# module_decode_opcodes.net
KiCad netlist of a schematic drawn in EAGLE
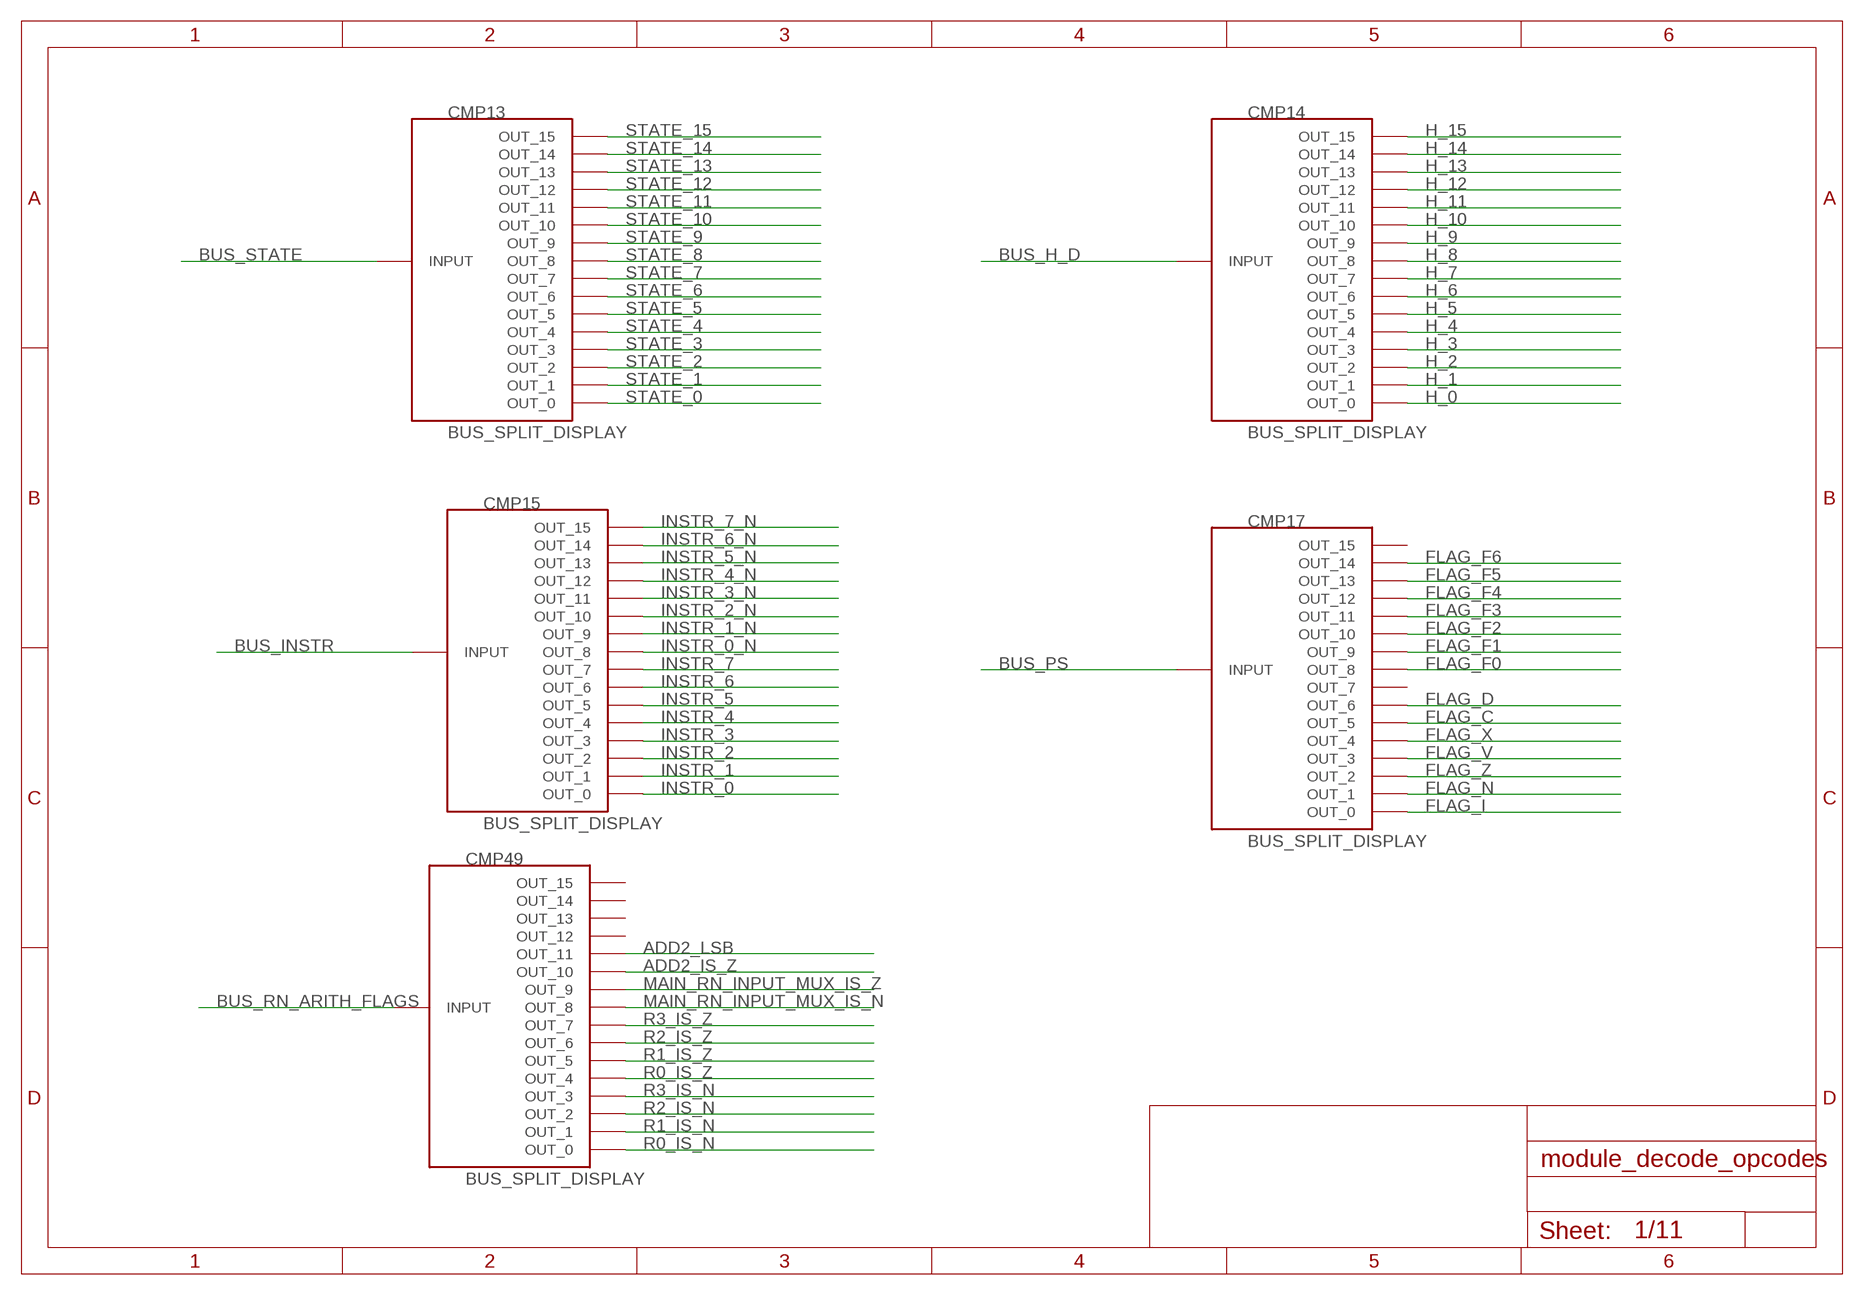
[diagram p0: schematic, sheet 1]
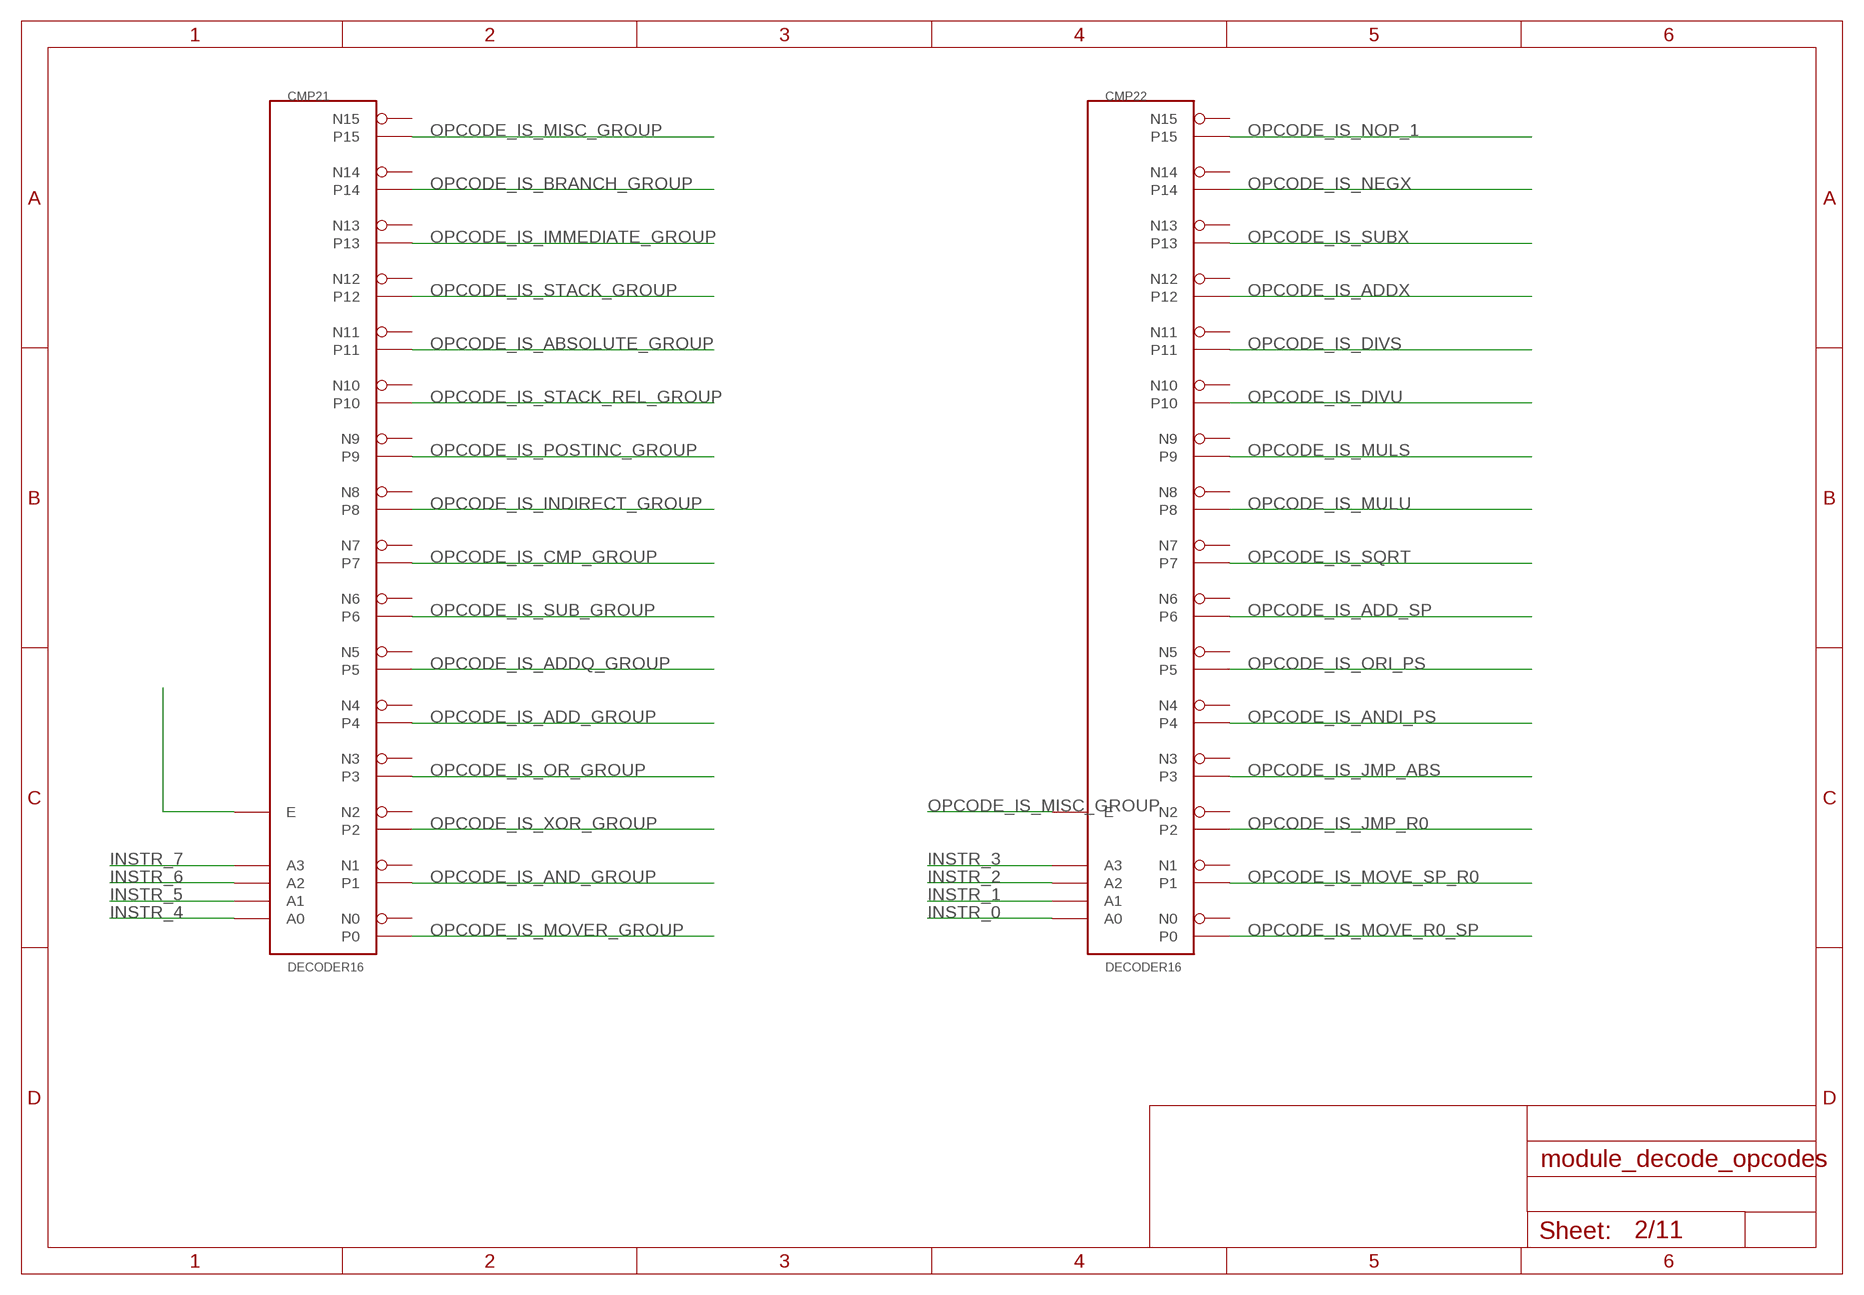
[diagram p1: schematic, sheet 2]
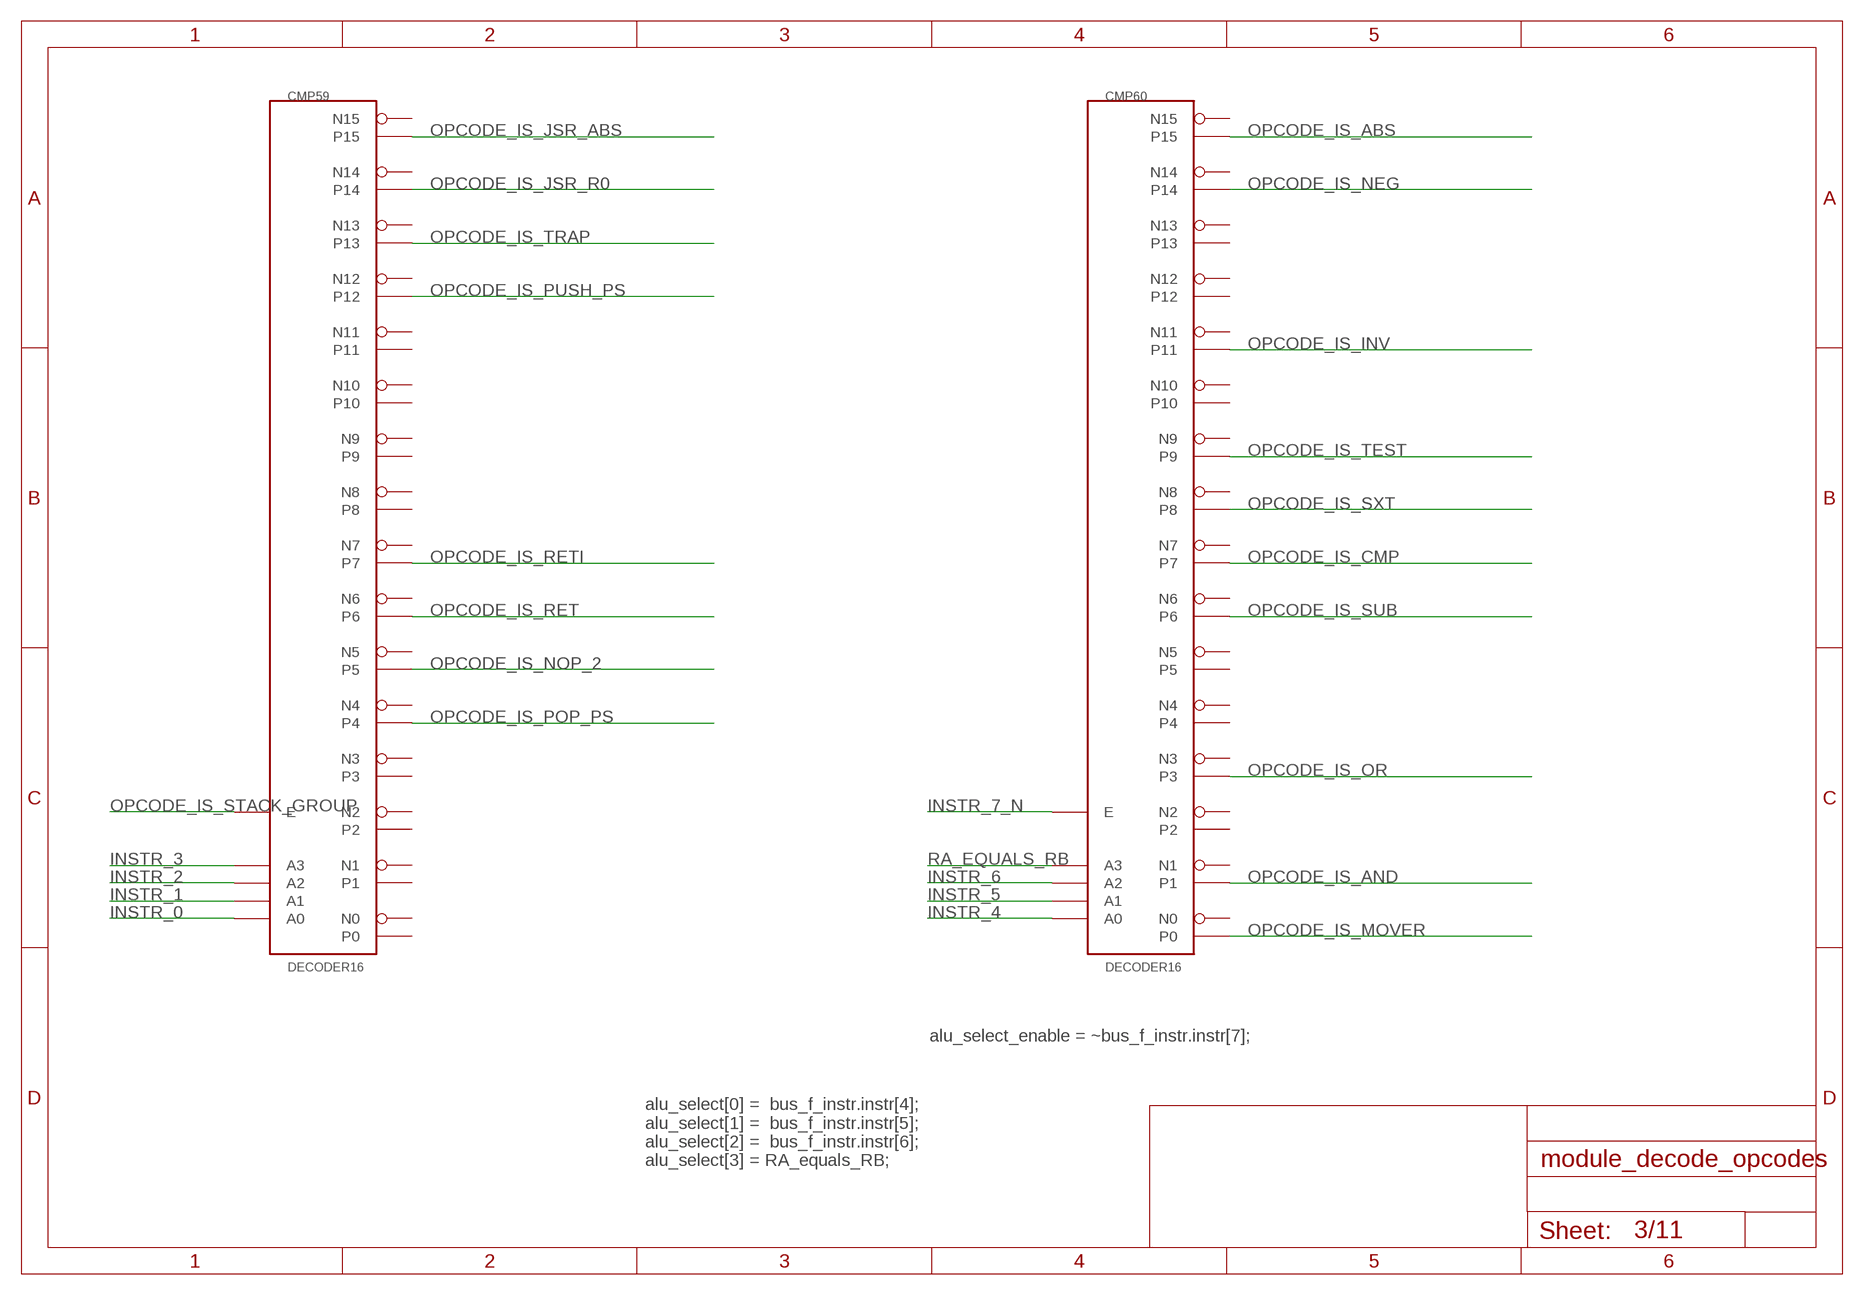
[diagram p2: schematic, sheet 3]
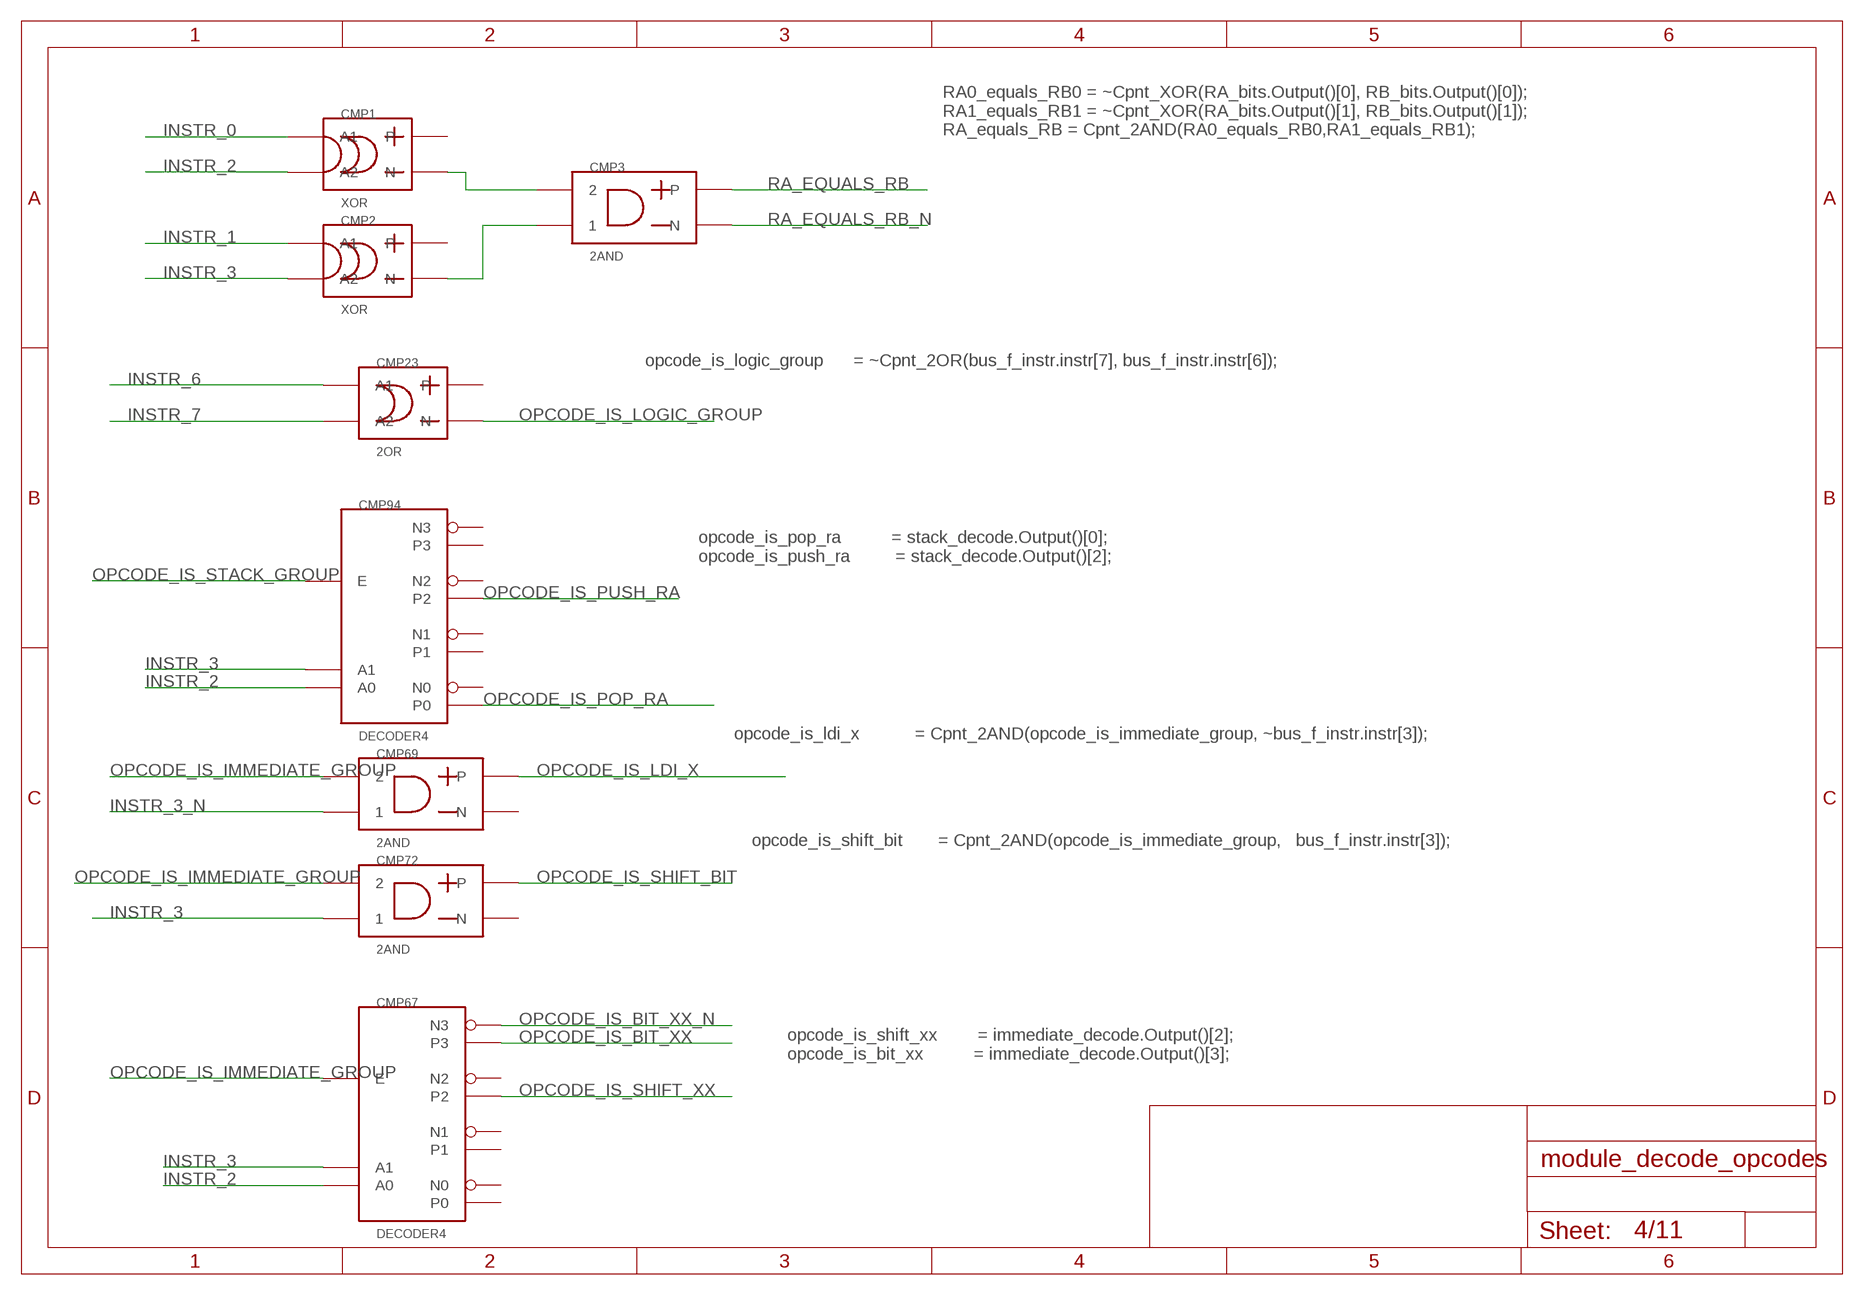
[diagram p3: schematic, sheet 4]
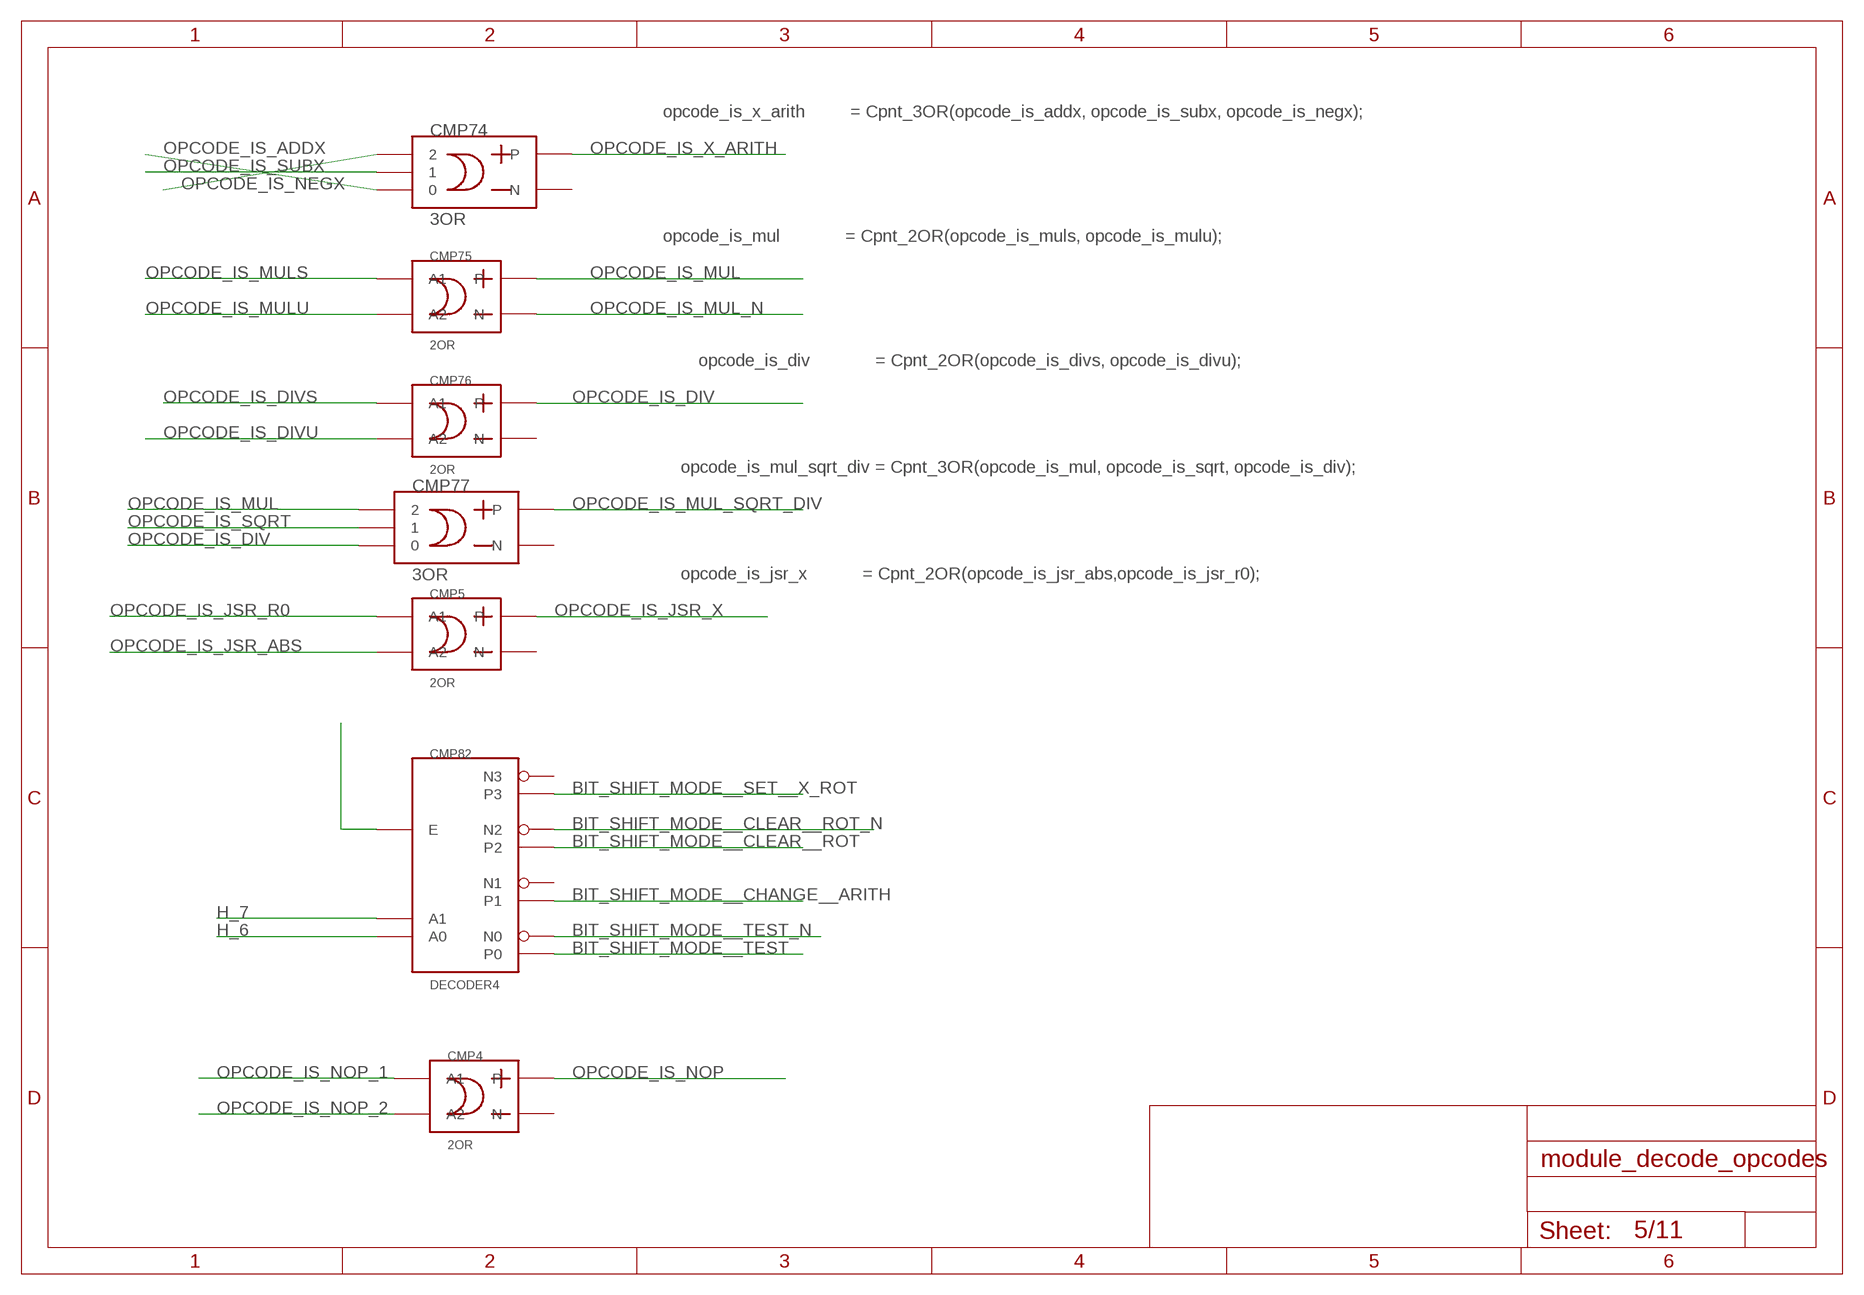
[diagram p4: schematic, sheet 5]
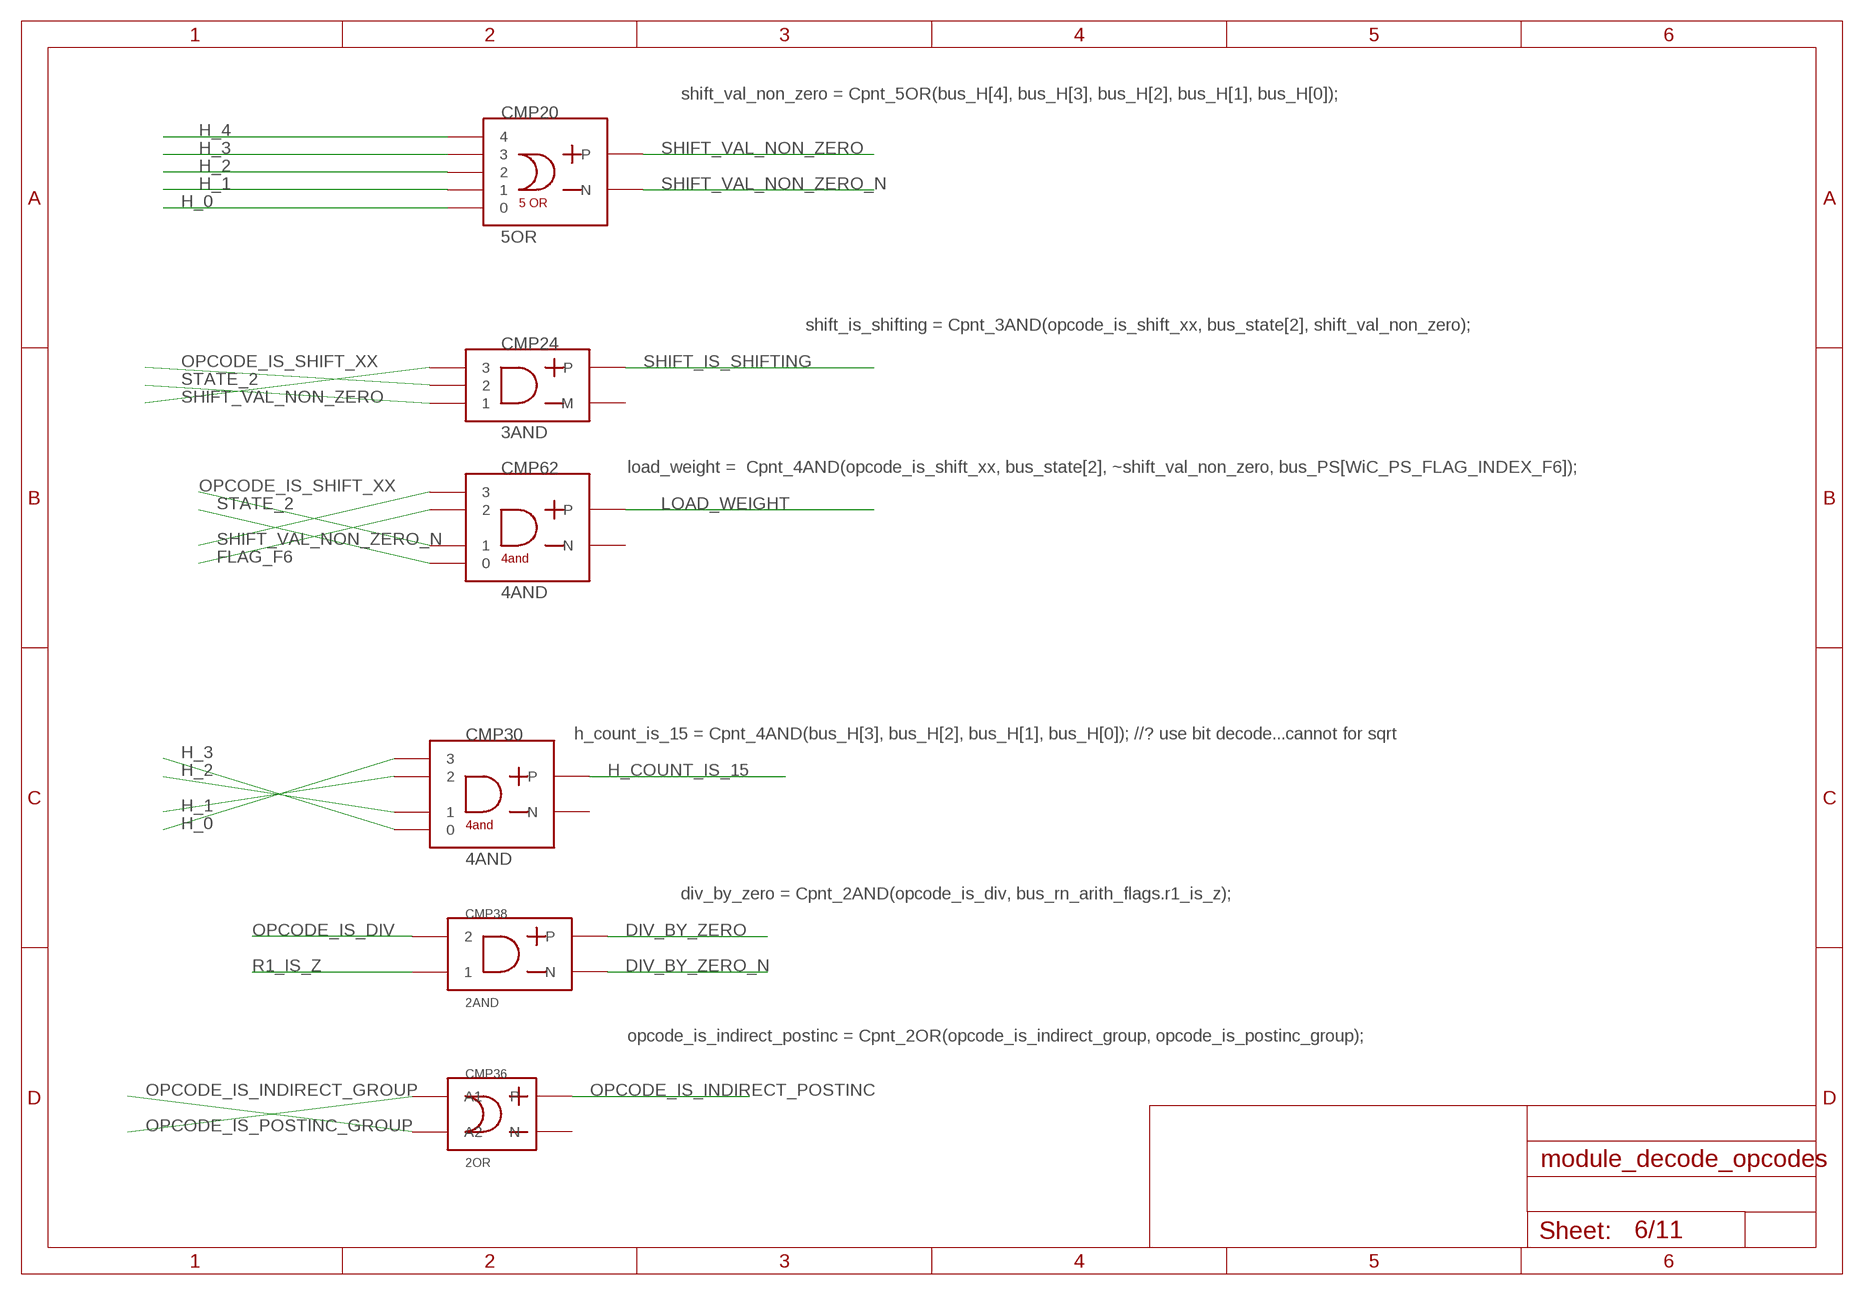
[diagram p5: schematic, sheet 6]
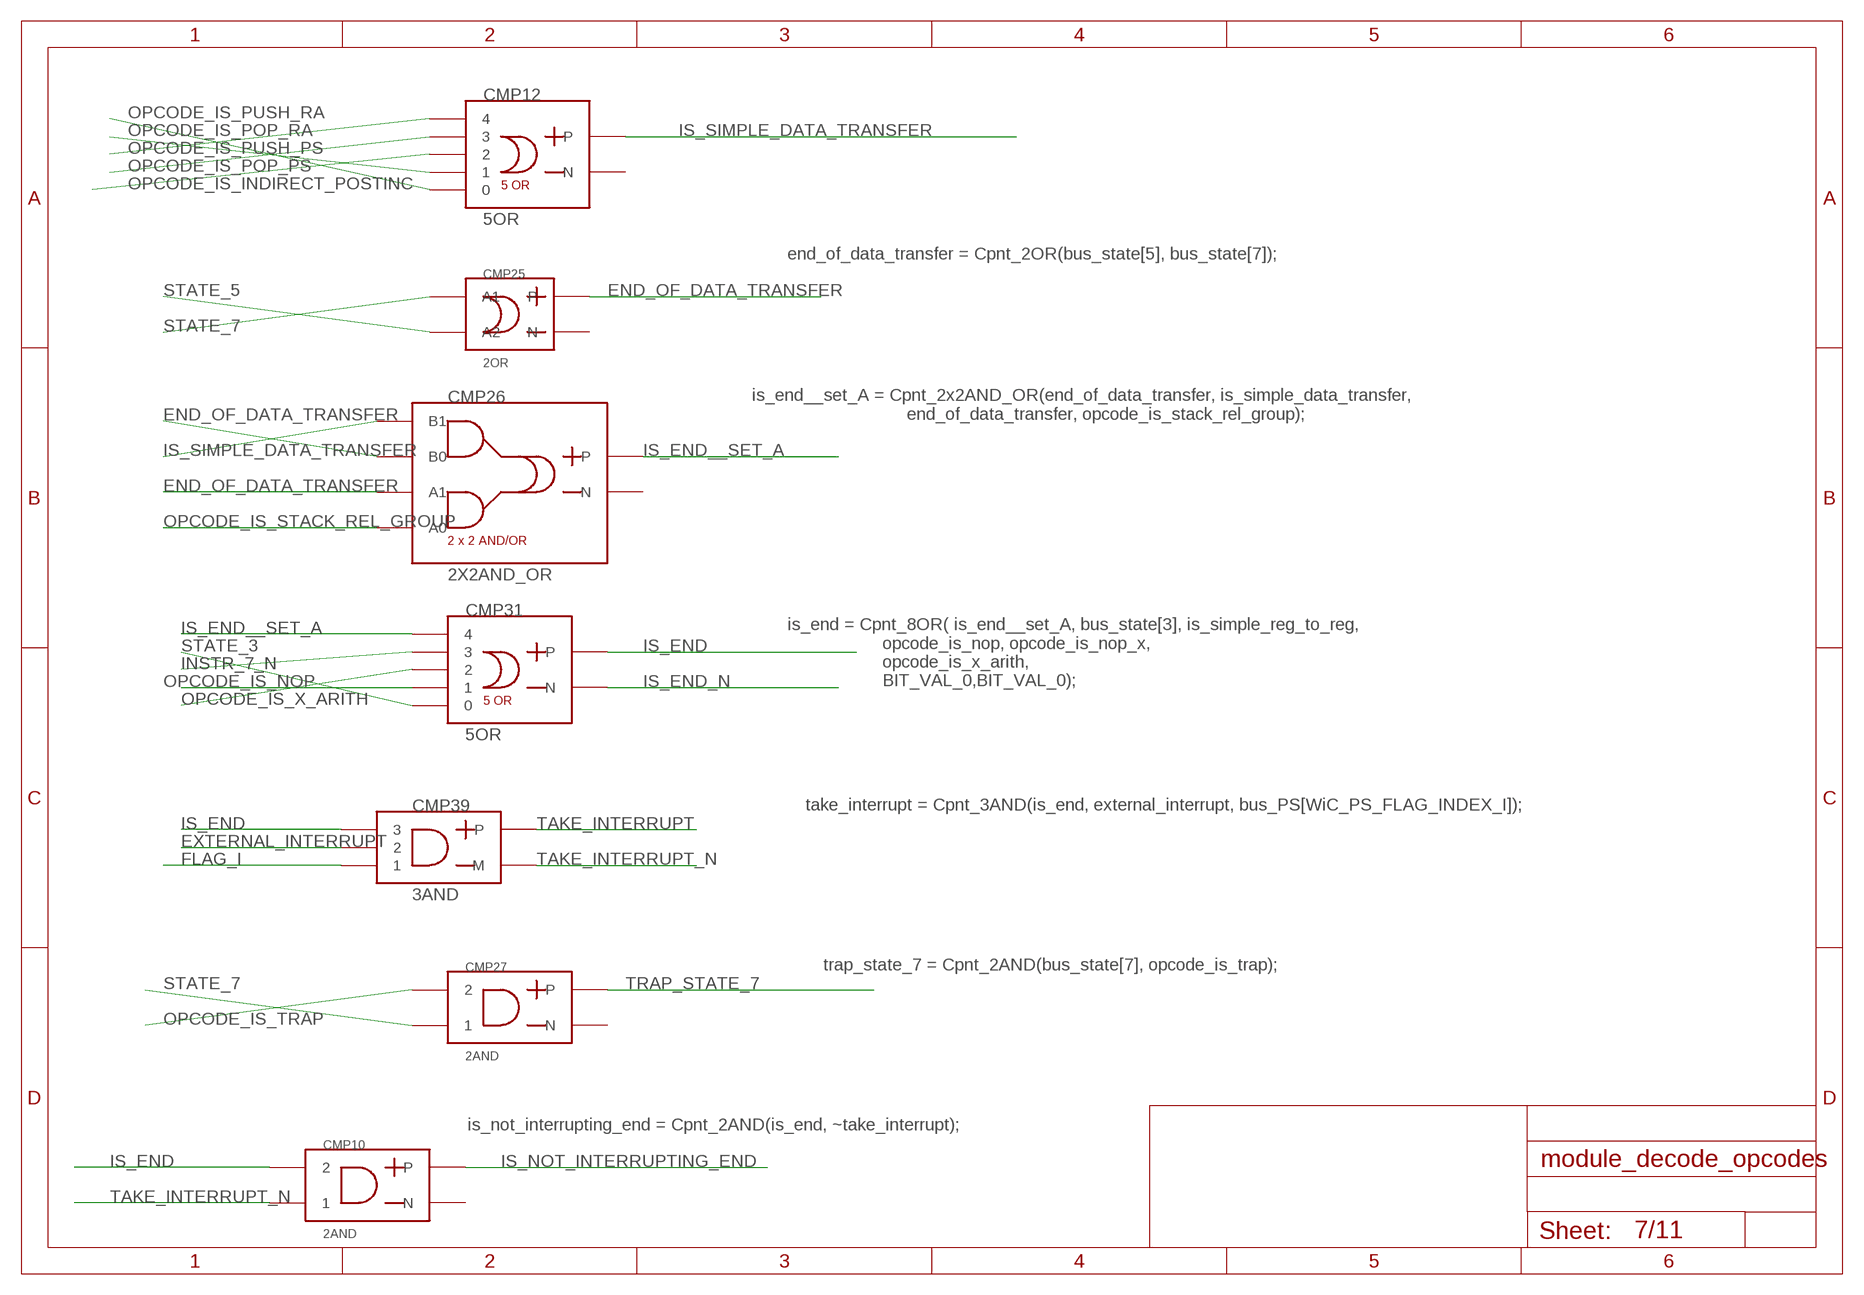
[diagram p6: schematic, sheet 7]
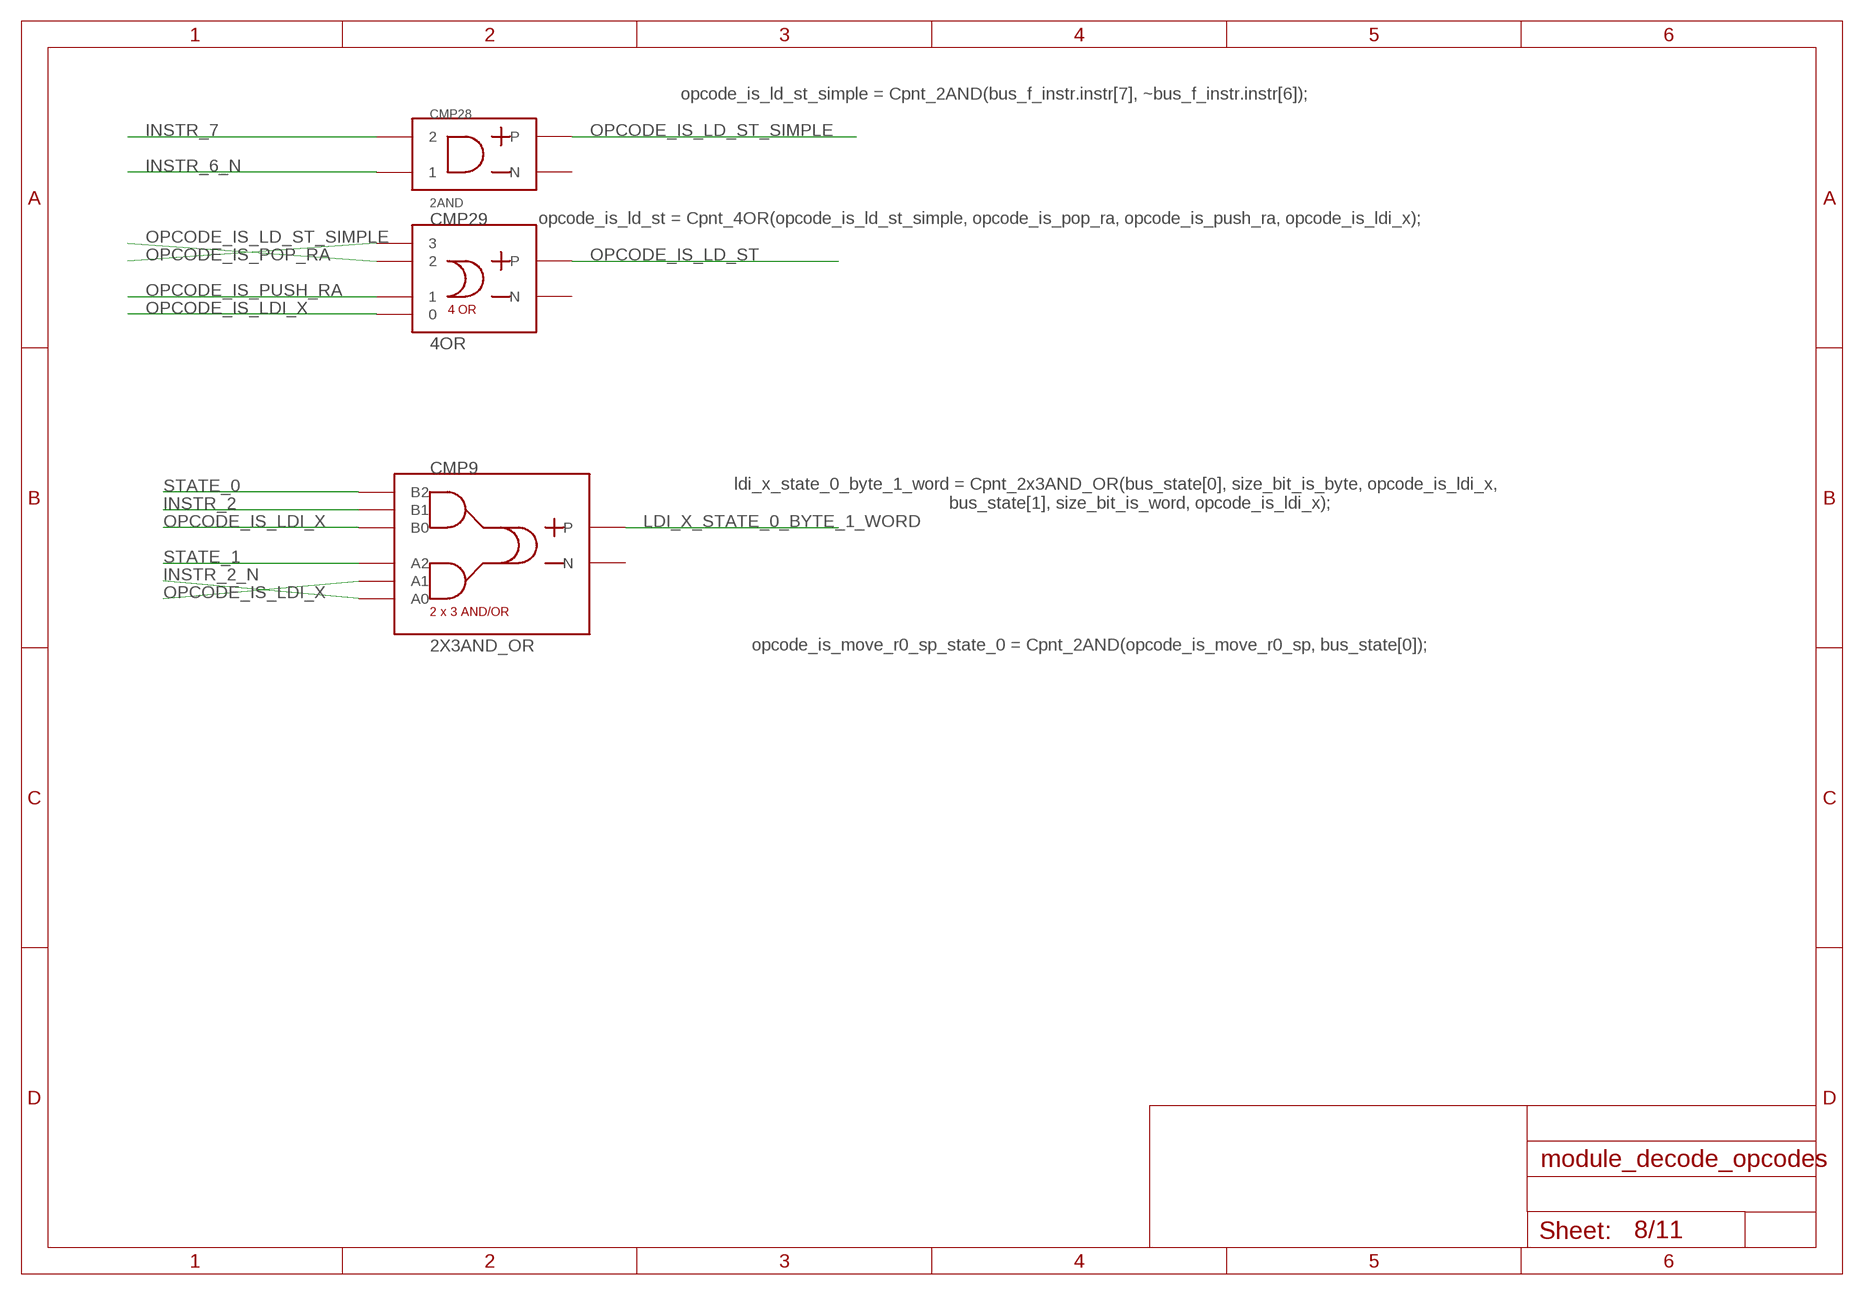
[diagram p7: schematic, sheet 8]
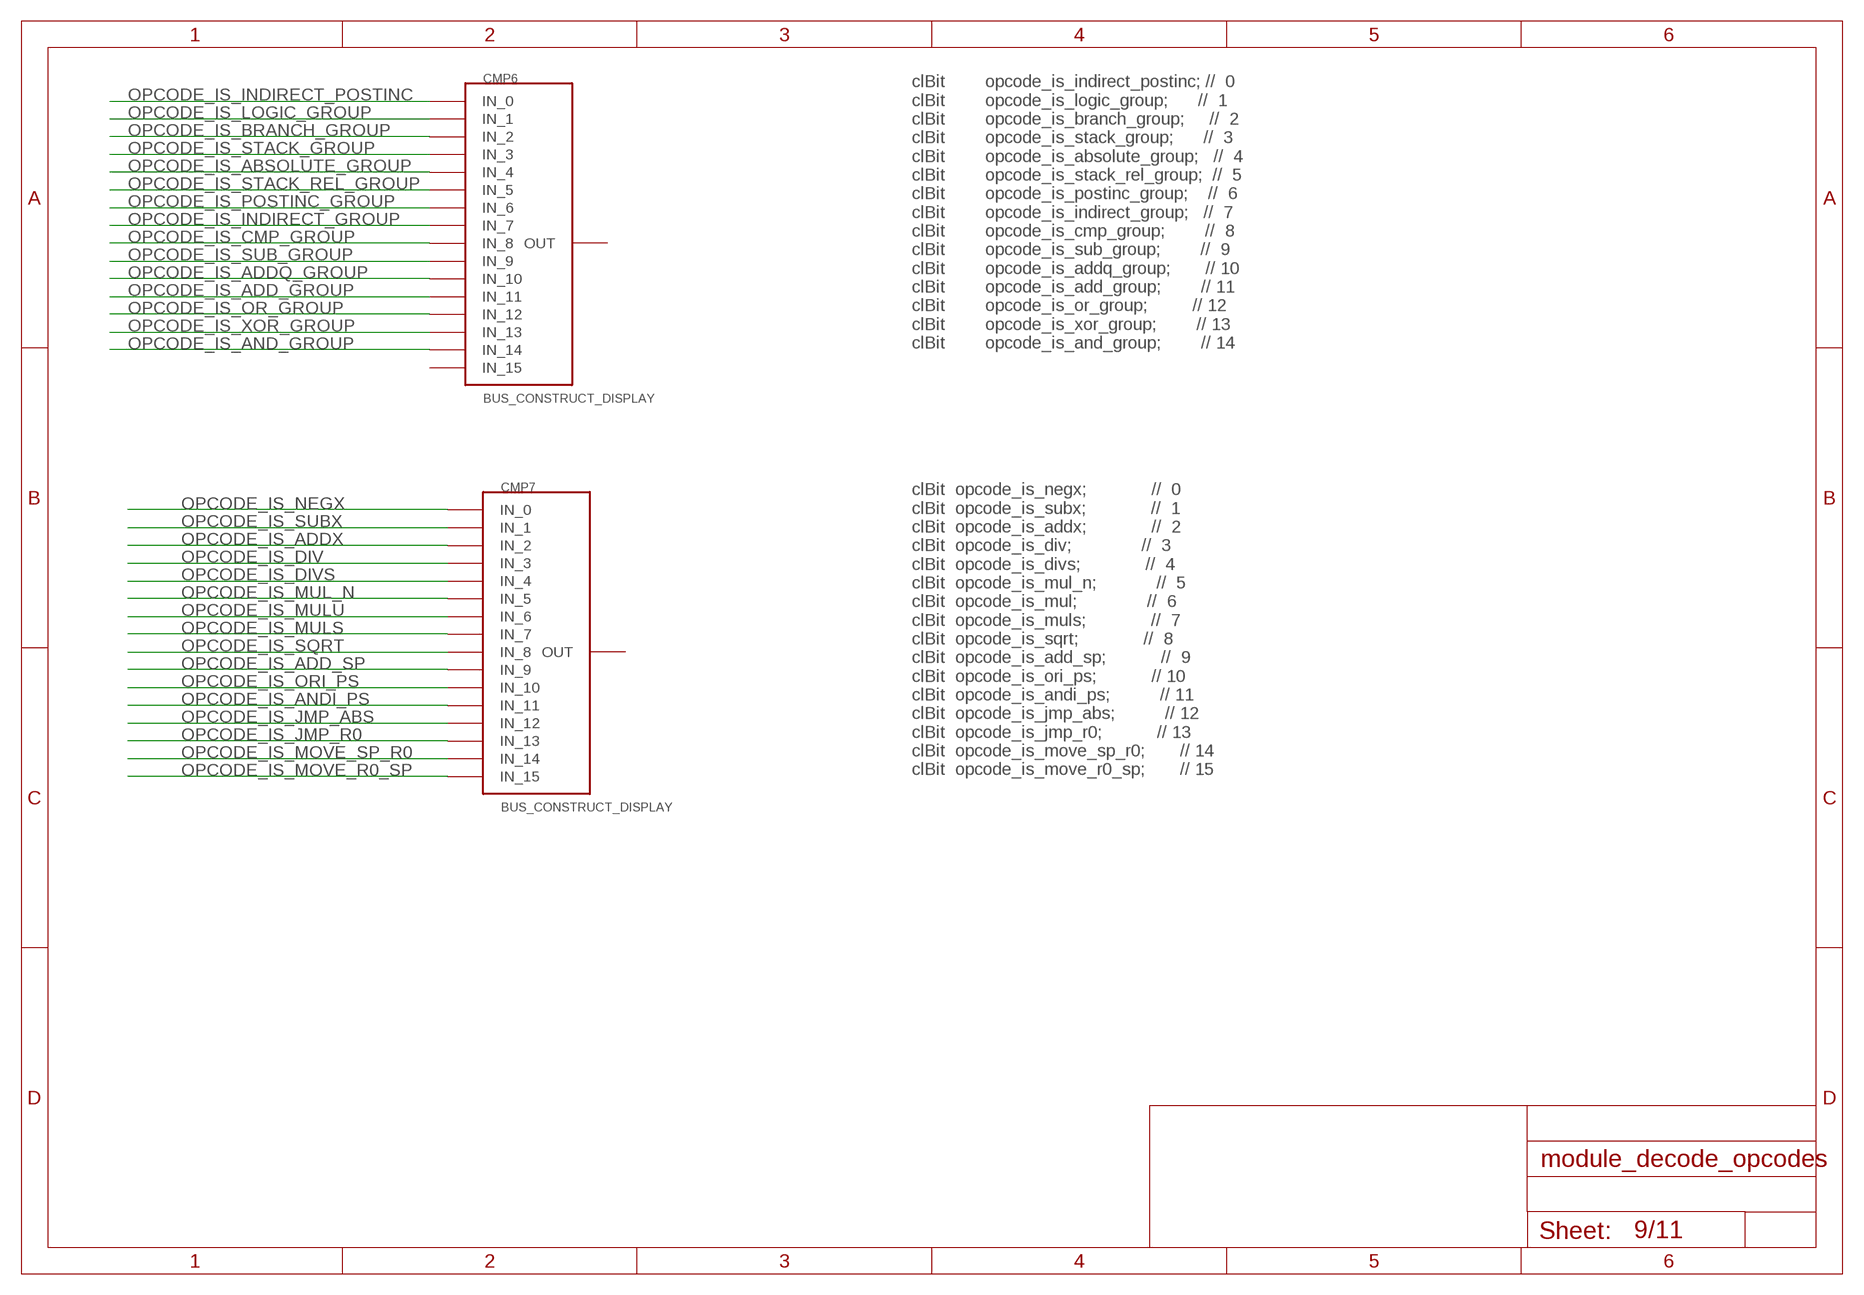
[diagram p8: schematic, sheet 9]
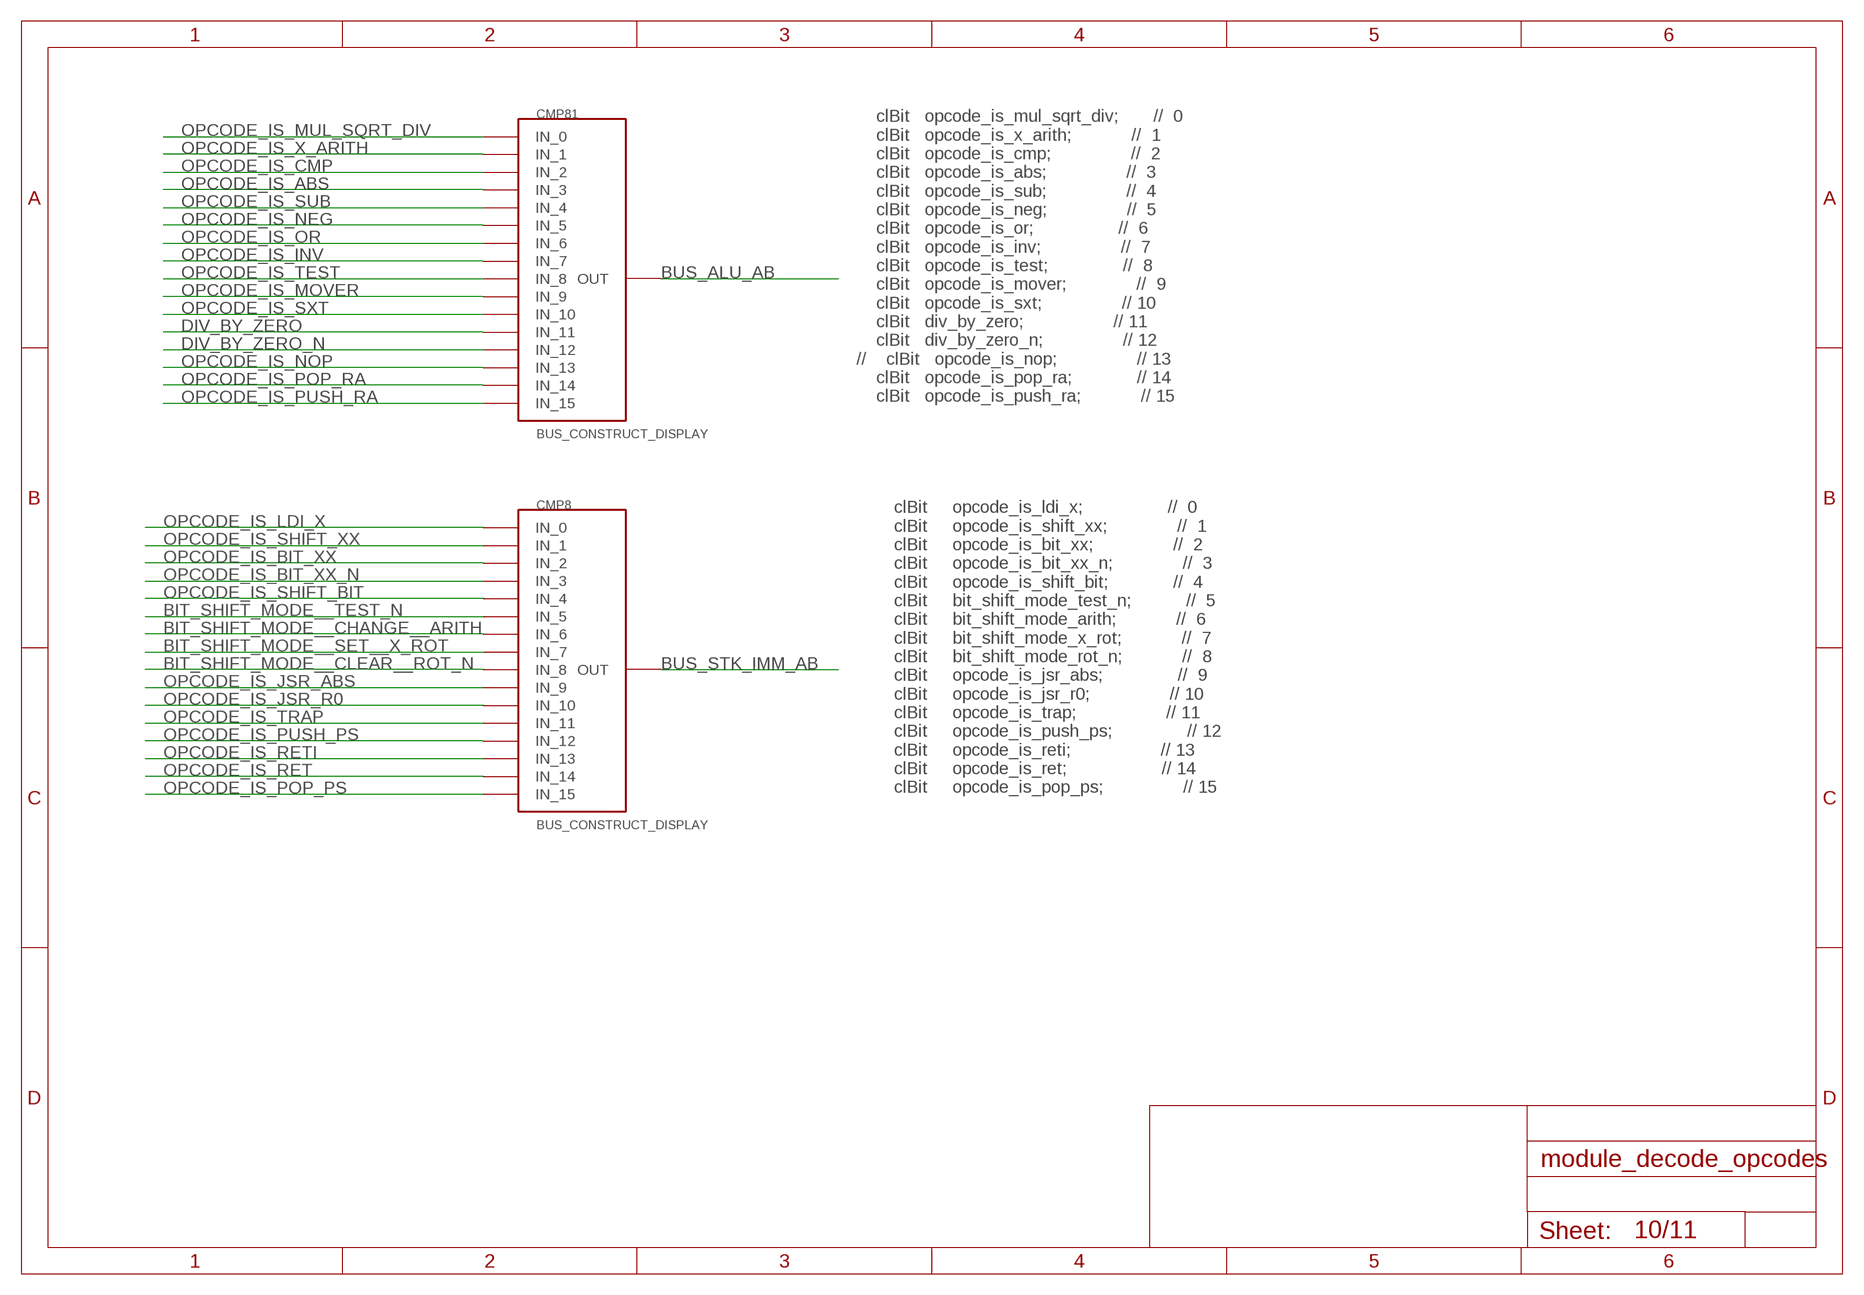
[diagram p9: schematic, sheet 10]
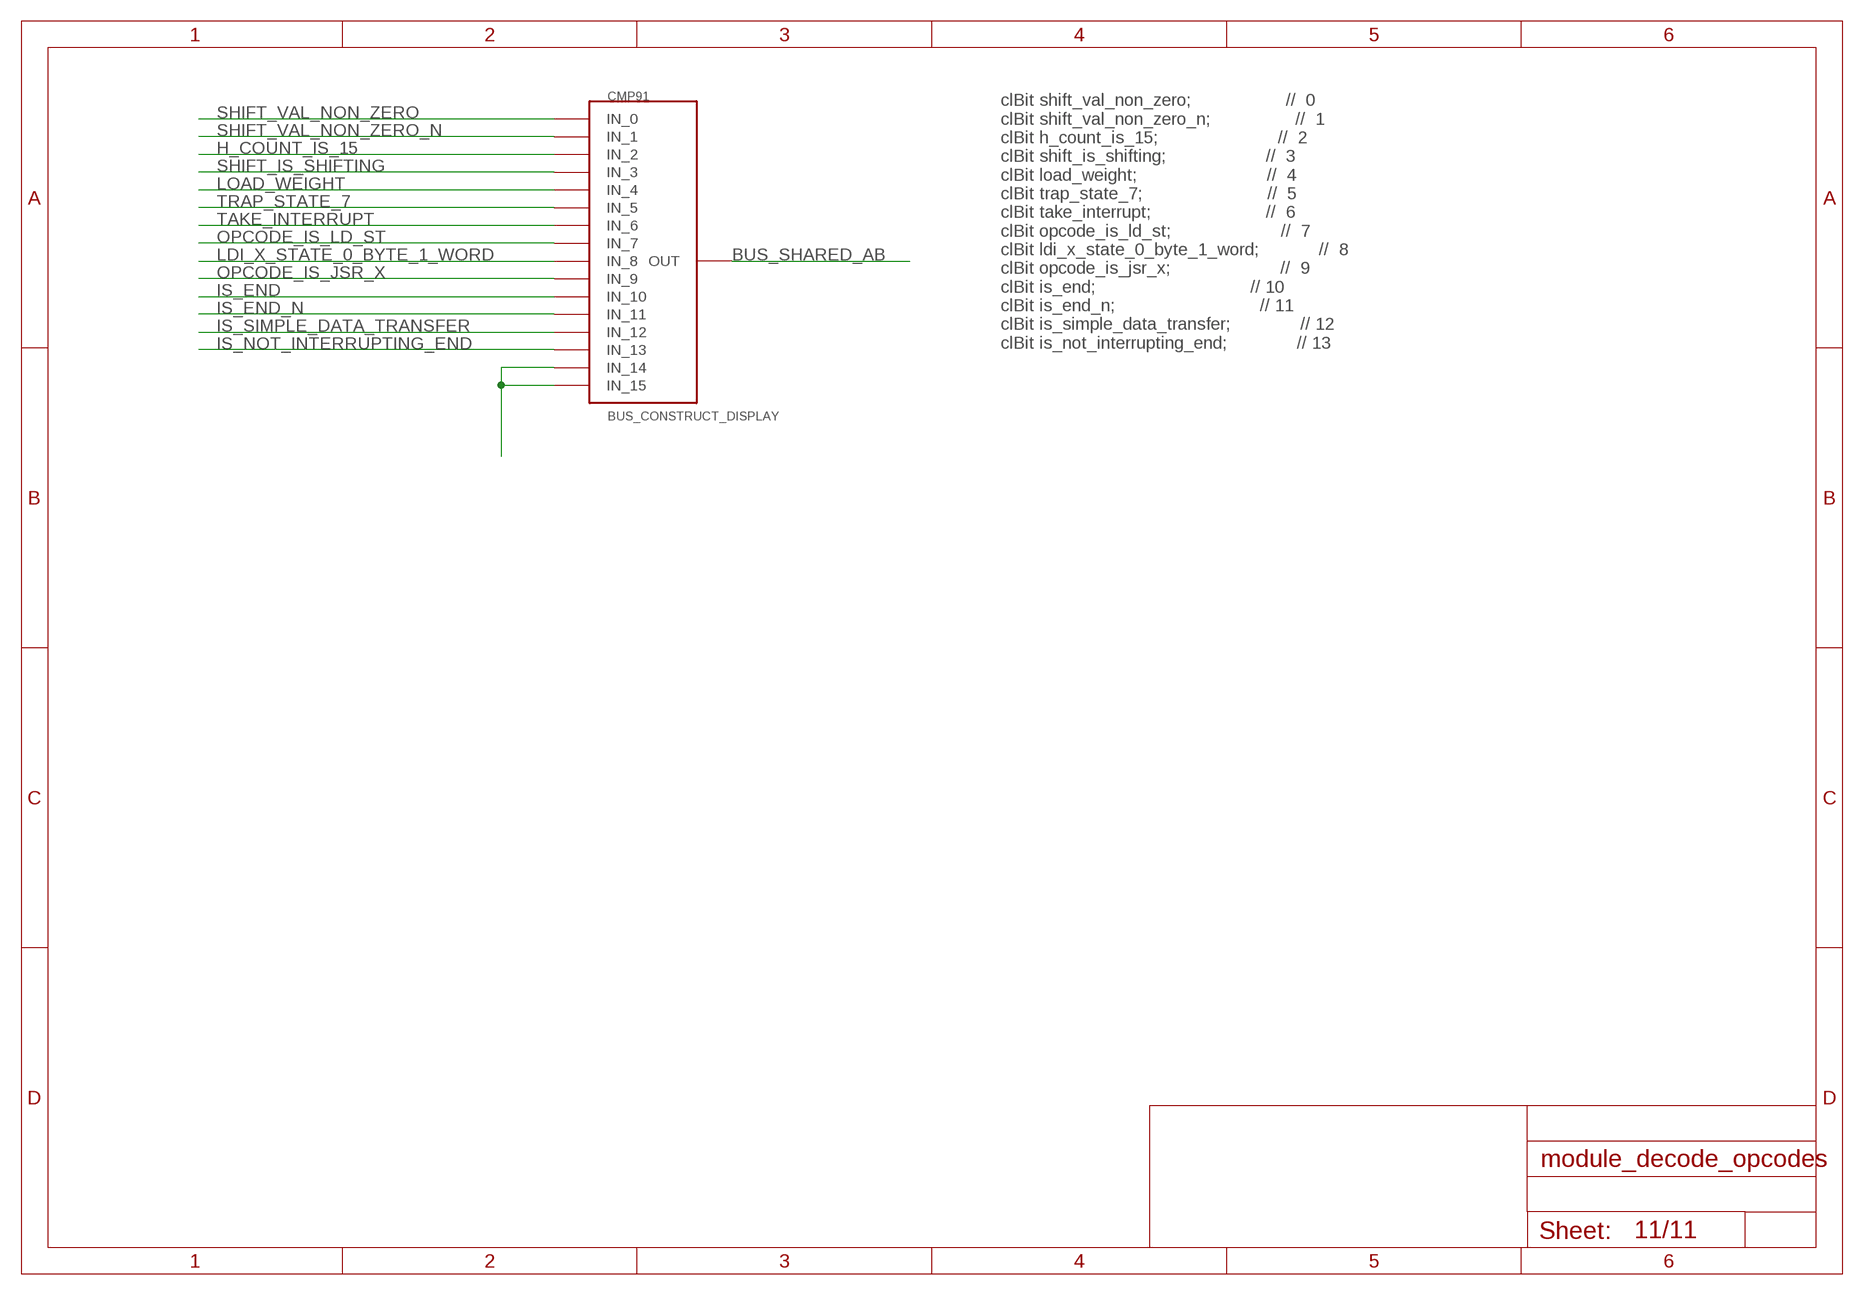
[diagram p10: schematic, sheet 11]

(export (version "E")
  (design (tool "Eeschema 10.0.6"))
  (components
    (comp (ref "CMP9")
      (value "2X3AND_OR")
      (footprint "eagle-import:2X3AND_OR")
      (libsource (lib "eagle-import") (part "2X3AND_OR"))
    )
    (comp (ref "CMP28")
      (value "2AND")
      (footprint "eagle-import:2AND")
      (libsource (lib "eagle-import") (part "2AND"))
    )
    (comp (ref "CMP29")
      (value "4OR")
      (footprint "eagle-import:4OR")
      (libsource (lib "eagle-import") (part "4OR"))
    )
    (comp (ref "CMP4")
      (value "2OR")
      (footprint "eagle-import:2OR")
      (libsource (lib "eagle-import") (part "2OR"))
    )
    (comp (ref "CMP5")
      (value "2OR")
      (footprint "eagle-import:2OR")
      (libsource (lib "eagle-import") (part "2OR"))
    )
    (comp (ref "CMP74")
      (value "3OR")
      (footprint "eagle-import:3OR")
      (libsource (lib "eagle-import") (part "3OR"))
    )
    (comp (ref "CMP75")
      (value "2OR")
      (footprint "eagle-import:2OR")
      (libsource (lib "eagle-import") (part "2OR"))
    )
    (comp (ref "CMP76")
      (value "2OR")
      (footprint "eagle-import:2OR")
      (libsource (lib "eagle-import") (part "2OR"))
    )
    (comp (ref "CMP77")
      (value "3OR")
      (footprint "eagle-import:3OR")
      (libsource (lib "eagle-import") (part "3OR"))
    )
    (comp (ref "CMP82")
      (value "DECODER4")
      (footprint "eagle-import:DECODER4")
      (libsource (lib "eagle-import") (part "DECODER4"))
    )
    (comp (ref "CMP91")
      (value "BUS_CONSTRUCT_DISPLAY")
      (footprint "eagle-import:BUS_SPLIT_DISPLAY")
      (libsource (lib "eagle-import") (part "BUS_CONSTRUCT_DISPLAY"))
    )
    (comp (ref "CMP1")
      (value "XOR")
      (footprint "eagle-import:XOR")
      (libsource (lib "eagle-import") (part "XOR"))
    )
    (comp (ref "CMP2")
      (value "XOR")
      (footprint "eagle-import:XOR")
      (libsource (lib "eagle-import") (part "XOR"))
    )
    (comp (ref "CMP3")
      (value "2AND")
      (footprint "eagle-import:2AND")
      (libsource (lib "eagle-import") (part "2AND"))
    )
    (comp (ref "CMP23")
      (value "2OR")
      (footprint "eagle-import:2OR")
      (libsource (lib "eagle-import") (part "2OR"))
    )
    (comp (ref "CMP67")
      (value "DECODER4")
      (footprint "eagle-import:DECODER4")
      (libsource (lib "eagle-import") (part "DECODER4"))
    )
    (comp (ref "CMP69")
      (value "2AND")
      (footprint "eagle-import:2AND")
      (libsource (lib "eagle-import") (part "2AND"))
    )
    (comp (ref "CMP72")
      (value "2AND")
      (footprint "eagle-import:2AND")
      (libsource (lib "eagle-import") (part "2AND"))
    )
    (comp (ref "CMP94")
      (value "DECODER4")
      (footprint "eagle-import:DECODER4")
      (libsource (lib "eagle-import") (part "DECODER4"))
    )
    (comp (ref "CMP59")
      (value "DECODER16")
      (footprint "eagle-import:DECODER16")
      (libsource (lib "eagle-import") (part "DECODER16"))
    )
    (comp (ref "CMP60")
      (value "DECODER16")
      (footprint "eagle-import:DECODER16")
      (libsource (lib "eagle-import") (part "DECODER16"))
    )
    (comp (ref "CMP13")
      (value "BUS_SPLIT_DISPLAY")
      (footprint "eagle-import:BUS_SPLIT_DISPLAY")
      (libsource (lib "eagle-import") (part "BUS_SPLIT_DISPLAY"))
    )
    (comp (ref "CMP14")
      (value "BUS_SPLIT_DISPLAY")
      (footprint "eagle-import:BUS_SPLIT_DISPLAY")
      (libsource (lib "eagle-import") (part "BUS_SPLIT_DISPLAY"))
    )
    (comp (ref "CMP15")
      (value "BUS_SPLIT_DISPLAY")
      (footprint "eagle-import:BUS_SPLIT_DISPLAY")
      (libsource (lib "eagle-import") (part "BUS_SPLIT_DISPLAY"))
    )
    (comp (ref "CMP17")
      (value "BUS_SPLIT_DISPLAY")
      (footprint "eagle-import:BUS_SPLIT_DISPLAY")
      (libsource (lib "eagle-import") (part "BUS_SPLIT_DISPLAY"))
    )
    (comp (ref "CMP49")
      (value "BUS_SPLIT_DISPLAY")
      (footprint "eagle-import:BUS_SPLIT_DISPLAY")
      (libsource (lib "eagle-import") (part "BUS_SPLIT_DISPLAY"))
    )
    (comp (ref "CMP10")
      (value "2AND")
      (footprint "eagle-import:2AND")
      (libsource (lib "eagle-import") (part "2AND"))
    )
    (comp (ref "CMP12")
      (value "5OR")
      (footprint "eagle-import:5OR")
      (libsource (lib "eagle-import") (part "5OR"))
    )
    (comp (ref "CMP25")
      (value "2OR")
      (footprint "eagle-import:2OR")
      (libsource (lib "eagle-import") (part "2OR"))
    )
    (comp (ref "CMP26")
      (value "2X2AND_OR")
      (footprint "eagle-import:2X2AND_OR")
      (libsource (lib "eagle-import") (part "2X2AND_OR"))
    )
    (comp (ref "CMP27")
      (value "2AND")
      (footprint "eagle-import:2AND")
      (libsource (lib "eagle-import") (part "2AND"))
    )
    (comp (ref "CMP31")
      (value "5OR")
      (footprint "eagle-import:5OR")
      (libsource (lib "eagle-import") (part "5OR"))
    )
    (comp (ref "CMP39")
      (value "3AND")
      (footprint "eagle-import:3AND")
      (libsource (lib "eagle-import") (part "3AND"))
    )
    (comp (ref "CMP21")
      (value "DECODER16")
      (footprint "eagle-import:DECODER16")
      (libsource (lib "eagle-import") (part "DECODER16"))
    )
    (comp (ref "CMP22")
      (value "DECODER16")
      (footprint "eagle-import:DECODER16")
      (libsource (lib "eagle-import") (part "DECODER16"))
    )
    (comp (ref "CMP6")
      (value "BUS_CONSTRUCT_DISPLAY")
      (footprint "eagle-import:BUS_SPLIT_DISPLAY")
      (libsource (lib "eagle-import") (part "BUS_CONSTRUCT_DISPLAY"))
    )
    (comp (ref "CMP7")
      (value "BUS_CONSTRUCT_DISPLAY")
      (footprint "eagle-import:BUS_SPLIT_DISPLAY")
      (libsource (lib "eagle-import") (part "BUS_CONSTRUCT_DISPLAY"))
    )
    (comp (ref "CMP8")
      (value "BUS_CONSTRUCT_DISPLAY")
      (footprint "eagle-import:BUS_SPLIT_DISPLAY")
      (libsource (lib "eagle-import") (part "BUS_CONSTRUCT_DISPLAY"))
    )
    (comp (ref "CMP81")
      (value "BUS_CONSTRUCT_DISPLAY")
      (footprint "eagle-import:BUS_SPLIT_DISPLAY")
      (libsource (lib "eagle-import") (part "BUS_CONSTRUCT_DISPLAY"))
    )
    (comp (ref "CMP20")
      (value "5OR")
      (footprint "eagle-import:5OR")
      (libsource (lib "eagle-import") (part "5OR"))
    )
    (comp (ref "CMP24")
      (value "3AND")
      (footprint "eagle-import:3AND")
      (libsource (lib "eagle-import") (part "3AND"))
    )
    (comp (ref "CMP30")
      (value "4AND")
      (footprint "eagle-import:4AND")
      (libsource (lib "eagle-import") (part "4AND"))
    )
    (comp (ref "CMP36")
      (value "2OR")
      (footprint "eagle-import:2OR")
      (libsource (lib "eagle-import") (part "2OR"))
    )
    (comp (ref "CMP38")
      (value "2AND")
      (footprint "eagle-import:2AND")
      (libsource (lib "eagle-import") (part "2AND"))
    )
    (comp (ref "CMP62")
      (value "4AND")
      (footprint "eagle-import:4AND")
      (libsource (lib "eagle-import") (part "4AND"))
    )
  )
  (nets
    (net (code "1") (name "ADD2_IS_Z") (class "Default")
      (node (ref "CMP49") (pin "P$11") (pinfunction "OUT_10_P$11") (pintype "output"))
    )
    (net (code "2") (name "ADD2_LSB") (class "Default")
      (node (ref "CMP49") (pin "P$12") (pinfunction "OUT_11_P$12") (pintype "output"))
    )
    (net (code "3") (name "BIT_SHIFT_MODE__CHANGE__ARITH") (class "Default")
      (node (ref "CMP8") (pin "P$7") (pinfunction "IN_6_P$7") (pintype "input"))
      (node (ref "CMP82") (pin "P1") (pinfunction "P1_P1") (pintype "output"))
    )
    (net (code "4") (name "BIT_SHIFT_MODE__CLEAR__ROT") (class "Default")
      (node (ref "CMP82") (pin "P2") (pinfunction "P2_P2") (pintype "output"))
    )
    (net (code "5") (name "BIT_SHIFT_MODE__CLEAR__ROT_N") (class "Default")
      (node (ref "CMP8") (pin "P$9") (pinfunction "IN_8_P$9") (pintype "input"))
      (node (ref "CMP82") (pin "N2") (pinfunction "N2_N2") (pintype "output"))
    )
    (net (code "6") (name "BIT_SHIFT_MODE__SET__X_ROT") (class "Default")
      (node (ref "CMP8") (pin "P$8") (pinfunction "IN_7_P$8") (pintype "input"))
      (node (ref "CMP82") (pin "P3") (pinfunction "P3_P3") (pintype "output"))
    )
    (net (code "7") (name "BIT_SHIFT_MODE__TEST") (class "Default")
      (node (ref "CMP82") (pin "P0") (pinfunction "P0_P0") (pintype "output"))
    )
    (net (code "8") (name "BIT_SHIFT_MODE__TEST_N") (class "Default")
      (node (ref "CMP8") (pin "P$6") (pinfunction "IN_5_P$6") (pintype "input"))
      (node (ref "CMP82") (pin "N0") (pinfunction "N0_N0") (pintype "output"))
    )
    (net (code "9") (name "BUS_ALU_AB") (class "Default")
      (node (ref "CMP81") (pin "INPUT") (pinfunction "OUT_INPUT") (pintype "output"))
    )
    (net (code "10") (name "BUS_H_D") (class "Default")
      (node (ref "CMP14") (pin "INPUT") (pinfunction "INPUT_INPUT") (pintype "input"))
    )
    (net (code "11") (name "BUS_INSTR") (class "Default")
      (node (ref "CMP15") (pin "INPUT") (pinfunction "INPUT_INPUT") (pintype "input"))
    )
    (net (code "12") (name "BUS_PS") (class "Default")
      (node (ref "CMP17") (pin "INPUT") (pinfunction "INPUT_INPUT") (pintype "input"))
    )
    (net (code "13") (name "BUS_RN_ARITH_FLAGS") (class "Default")
      (node (ref "CMP49") (pin "INPUT") (pinfunction "INPUT_INPUT") (pintype "input"))
    )
    (net (code "14") (name "BUS_SHARED_AB") (class "Default")
      (node (ref "CMP91") (pin "INPUT") (pinfunction "OUT_INPUT") (pintype "output"))
    )
    (net (code "15") (name "BUS_STATE") (class "Default")
      (node (ref "CMP13") (pin "INPUT") (pinfunction "INPUT_INPUT") (pintype "input"))
    )
    (net (code "16") (name "BUS_STK_IMM_AB") (class "Default")
      (node (ref "CMP8") (pin "INPUT") (pinfunction "OUT_INPUT") (pintype "output"))
    )
    (net (code "17") (name "DIV_BY_ZERO") (class "Default")
      (node (ref "CMP38") (pin "OUT_P") (pinfunction "P_OUT_P") (pintype "output"))
      (node (ref "CMP81") (pin "P$12") (pinfunction "IN_11_P$12") (pintype "input"))
    )
    (net (code "18") (name "DIV_BY_ZERO_N") (class "Default")
      (node (ref "CMP38") (pin "OUT_M") (pinfunction "N_OUT_M") (pintype "output"))
      (node (ref "CMP81") (pin "P$13") (pinfunction "IN_12_P$13") (pintype "input"))
    )
    (net (code "19") (name "END_OF_DATA_TRANSFER") (class "Default")
      (node (ref "CMP25") (pin "OUT_P") (pinfunction "P_OUT_P") (pintype "output"))
      (node (ref "CMP26") (pin "P$2") (pinfunction "A1_P$2") (pintype "input"))
      (node (ref "CMP26") (pin "P$3") (pinfunction "B0_P$3") (pintype "input"))
    )
    (net (code "20") (name "EXTERNAL_INTERRUPT") (class "Default")
      (node (ref "CMP39") (pin "P$2") (pinfunction "2_P$2") (pintype "input"))
    )
    (net (code "21") (name "FLAG_C") (class "Default")
      (node (ref "CMP17") (pin "P$6") (pinfunction "OUT_5_P$6") (pintype "output"))
    )
    (net (code "22") (name "FLAG_D") (class "Default")
      (node (ref "CMP17") (pin "P$7") (pinfunction "OUT_6_P$7") (pintype "output"))
    )
    (net (code "23") (name "FLAG_F0") (class "Default")
      (node (ref "CMP17") (pin "P$9") (pinfunction "OUT_8_P$9") (pintype "output"))
    )
    (net (code "24") (name "FLAG_F1") (class "Default")
      (node (ref "CMP17") (pin "P$10") (pinfunction "OUT_9_P$10") (pintype "output"))
    )
    (net (code "25") (name "FLAG_F2") (class "Default")
      (node (ref "CMP17") (pin "P$11") (pinfunction "OUT_10_P$11") (pintype "output"))
    )
    (net (code "26") (name "FLAG_F3") (class "Default")
      (node (ref "CMP17") (pin "P$12") (pinfunction "OUT_11_P$12") (pintype "output"))
    )
    (net (code "27") (name "FLAG_F4") (class "Default")
      (node (ref "CMP17") (pin "P$13") (pinfunction "OUT_12_P$13") (pintype "output"))
    )
    (net (code "28") (name "FLAG_F5") (class "Default")
      (node (ref "CMP17") (pin "P$14") (pinfunction "OUT_13_P$14") (pintype "output"))
    )
    (net (code "29") (name "FLAG_F6") (class "Default")
      (node (ref "CMP17") (pin "P$15") (pinfunction "OUT_14_P$15") (pintype "output"))
      (node (ref "CMP62") (pin "P$3") (pinfunction "2_P$3") (pintype "input"))
    )
    (net (code "30") (name "FLAG_I") (class "Default")
      (node (ref "CMP17") (pin "P$1") (pinfunction "OUT_0_P$1") (pintype "output"))
      (node (ref "CMP39") (pin "P$1") (pinfunction "1_P$1") (pintype "input"))
    )
    (net (code "31") (name "FLAG_N") (class "Default")
      (node (ref "CMP17") (pin "P$2") (pinfunction "OUT_1_P$2") (pintype "output"))
    )
    (net (code "32") (name "FLAG_V") (class "Default")
      (node (ref "CMP17") (pin "P$4") (pinfunction "OUT_3_P$4") (pintype "output"))
    )
    (net (code "33") (name "FLAG_X") (class "Default")
      (node (ref "CMP17") (pin "P$5") (pinfunction "OUT_4_P$5") (pintype "output"))
    )
    (net (code "34") (name "FLAG_Z") (class "Default")
      (node (ref "CMP17") (pin "P$3") (pinfunction "OUT_2_P$3") (pintype "output"))
    )
    (net (code "35") (name "H_0") (class "Default")
      (node (ref "CMP14") (pin "P$1") (pinfunction "OUT_0_P$1") (pintype "output"))
      (node (ref "CMP20") (pin "1") (pinfunction "0_1") (pintype "input"))
      (node (ref "CMP30") (pin "P$4") (pinfunction "3_P$4") (pintype "input"))
    )
    (net (code "36") (name "H_1") (class "Default")
      (node (ref "CMP14") (pin "P$2") (pinfunction "OUT_1_P$2") (pintype "output"))
      (node (ref "CMP20") (pin "2") (pinfunction "1_2") (pintype "input"))
      (node (ref "CMP30") (pin "P$3") (pinfunction "2_P$3") (pintype "input"))
    )
    (net (code "37") (name "H_2") (class "Default")
      (node (ref "CMP14") (pin "P$3") (pinfunction "OUT_2_P$3") (pintype "output"))
      (node (ref "CMP20") (pin "3") (pinfunction "2_3") (pintype "input"))
      (node (ref "CMP30") (pin "P$2") (pinfunction "1_P$2") (pintype "input"))
    )
    (net (code "38") (name "H_3") (class "Default")
      (node (ref "CMP14") (pin "P$4") (pinfunction "OUT_3_P$4") (pintype "output"))
      (node (ref "CMP20") (pin "4") (pinfunction "3_4") (pintype "input"))
      (node (ref "CMP30") (pin "P$1") (pinfunction "0_P$1") (pintype "input"))
    )
    (net (code "39") (name "H_4") (class "Default")
      (node (ref "CMP14") (pin "P$5") (pinfunction "OUT_4_P$5") (pintype "output"))
      (node (ref "CMP20") (pin "5") (pinfunction "4_5") (pintype "input"))
    )
    (net (code "40") (name "H_5") (class "Default")
      (node (ref "CMP14") (pin "P$6") (pinfunction "OUT_5_P$6") (pintype "output"))
    )
    (net (code "41") (name "H_6") (class "Default")
      (node (ref "CMP14") (pin "P$7") (pinfunction "OUT_6_P$7") (pintype "output"))
      (node (ref "CMP82") (pin "A0") (pinfunction "A0_A0") (pintype "input"))
    )
    (net (code "42") (name "H_7") (class "Default")
      (node (ref "CMP14") (pin "P$8") (pinfunction "OUT_7_P$8") (pintype "output"))
      (node (ref "CMP82") (pin "A1") (pinfunction "A1_A1") (pintype "input"))
    )
    (net (code "43") (name "H_8") (class "Default")
      (node (ref "CMP14") (pin "P$9") (pinfunction "OUT_8_P$9") (pintype "output"))
    )
    (net (code "44") (name "H_9") (class "Default")
      (node (ref "CMP14") (pin "P$10") (pinfunction "OUT_9_P$10") (pintype "output"))
    )
    (net (code "45") (name "H_10") (class "Default")
      (node (ref "CMP14") (pin "P$11") (pinfunction "OUT_10_P$11") (pintype "output"))
    )
    (net (code "46") (name "H_11") (class "Default")
      (node (ref "CMP14") (pin "P$12") (pinfunction "OUT_11_P$12") (pintype "output"))
    )
    (net (code "47") (name "H_12") (class "Default")
      (node (ref "CMP14") (pin "P$13") (pinfunction "OUT_12_P$13") (pintype "output"))
    )
    (net (code "48") (name "H_13") (class "Default")
      (node (ref "CMP14") (pin "P$14") (pinfunction "OUT_13_P$14") (pintype "output"))
    )
    (net (code "49") (name "H_14") (class "Default")
      (node (ref "CMP14") (pin "P$15") (pinfunction "OUT_14_P$15") (pintype "output"))
    )
    (net (code "50") (name "H_15") (class "Default")
      (node (ref "CMP14") (pin "P$16") (pinfunction "OUT_15_P$16") (pintype "output"))
    )
    (net (code "51") (name "H_COUNT_IS_15") (class "Default")
      (node (ref "CMP30") (pin "OUT_P") (pinfunction "P_OUT_P") (pintype "output"))
      (node (ref "CMP91") (pin "P$3") (pinfunction "IN_2_P$3") (pintype "input"))
    )
    (net (code "52") (name "INSTR_0") (class "Default")
      (node (ref "CMP1") (pin "P$1") (pinfunction "A1_P$1") (pintype "input"))
      (node (ref "CMP15") (pin "P$1") (pinfunction "OUT_0_P$1") (pintype "output"))
      (node (ref "CMP22") (pin "A0") (pinfunction "A0_A0") (pintype "input"))
      (node (ref "CMP59") (pin "A0") (pinfunction "A0_A0") (pintype "input"))
    )
    (net (code "53") (name "INSTR_0_N") (class "Default")
      (node (ref "CMP15") (pin "P$9") (pinfunction "OUT_8_P$9") (pintype "output"))
    )
    (net (code "54") (name "INSTR_1") (class "Default")
      (node (ref "CMP15") (pin "P$2") (pinfunction "OUT_1_P$2") (pintype "output"))
      (node (ref "CMP2") (pin "P$1") (pinfunction "A1_P$1") (pintype "input"))
      (node (ref "CMP22") (pin "A1") (pinfunction "A1_A1") (pintype "input"))
      (node (ref "CMP59") (pin "A1") (pinfunction "A1_A1") (pintype "input"))
    )
    (net (code "55") (name "INSTR_1_N") (class "Default")
      (node (ref "CMP15") (pin "P$10") (pinfunction "OUT_9_P$10") (pintype "output"))
    )
    (net (code "56") (name "INSTR_2") (class "Default")
      (node (ref "CMP1") (pin "P$2") (pinfunction "A2_P$2") (pintype "input"))
      (node (ref "CMP15") (pin "P$3") (pinfunction "OUT_2_P$3") (pintype "output"))
      (node (ref "CMP22") (pin "A2") (pinfunction "A2_A2") (pintype "input"))
      (node (ref "CMP59") (pin "A2") (pinfunction "A2_A2") (pintype "input"))
      (node (ref "CMP67") (pin "A0") (pinfunction "A0_A0") (pintype "input"))
      (node (ref "CMP9") (pin "P$5") (pinfunction "B1_P$5") (pintype "input"))
      (node (ref "CMP94") (pin "A0") (pinfunction "A0_A0") (pintype "input"))
    )
    (net (code "57") (name "INSTR_2_N") (class "Default")
      (node (ref "CMP15") (pin "P$11") (pinfunction "OUT_10_P$11") (pintype "output"))
      (node (ref "CMP9") (pin "P$1") (pinfunction "A0_P$1") (pintype "input"))
    )
    (net (code "58") (name "INSTR_3") (class "Default")
      (node (ref "CMP15") (pin "P$4") (pinfunction "OUT_3_P$4") (pintype "output"))
      (node (ref "CMP2") (pin "P$2") (pinfunction "A2_P$2") (pintype "input"))
      (node (ref "CMP22") (pin "A3") (pinfunction "A3_A3") (pintype "input"))
      (node (ref "CMP59") (pin "A3") (pinfunction "A3_A3") (pintype "input"))
      (node (ref "CMP67") (pin "A1") (pinfunction "A1_A1") (pintype "input"))
      (node (ref "CMP72") (pin "P$1") (pinfunction "1_P$1") (pintype "input"))
      (node (ref "CMP94") (pin "A1") (pinfunction "A1_A1") (pintype "input"))
    )
    (net (code "59") (name "INSTR_3_N") (class "Default")
      (node (ref "CMP15") (pin "P$12") (pinfunction "OUT_11_P$12") (pintype "output"))
      (node (ref "CMP69") (pin "P$1") (pinfunction "1_P$1") (pintype "input"))
    )
    (net (code "60") (name "INSTR_4") (class "Default")
      (node (ref "CMP15") (pin "P$5") (pinfunction "OUT_4_P$5") (pintype "output"))
      (node (ref "CMP21") (pin "A0") (pinfunction "A0_A0") (pintype "input"))
      (node (ref "CMP60") (pin "A0") (pinfunction "A0_A0") (pintype "input"))
    )
    (net (code "61") (name "INSTR_4_N") (class "Default")
      (node (ref "CMP15") (pin "P$13") (pinfunction "OUT_12_P$13") (pintype "output"))
    )
    (net (code "62") (name "INSTR_5") (class "Default")
      (node (ref "CMP15") (pin "P$6") (pinfunction "OUT_5_P$6") (pintype "output"))
      (node (ref "CMP21") (pin "A1") (pinfunction "A1_A1") (pintype "input"))
      (node (ref "CMP60") (pin "A1") (pinfunction "A1_A1") (pintype "input"))
    )
    (net (code "63") (name "INSTR_5_N") (class "Default")
      (node (ref "CMP15") (pin "P$14") (pinfunction "OUT_13_P$14") (pintype "output"))
    )
    (net (code "64") (name "INSTR_6") (class "Default")
      (node (ref "CMP15") (pin "P$7") (pinfunction "OUT_6_P$7") (pintype "output"))
      (node (ref "CMP21") (pin "A2") (pinfunction "A2_A2") (pintype "input"))
      (node (ref "CMP23") (pin "P$2") (pinfunction "A1_P$2") (pintype "input"))
      (node (ref "CMP60") (pin "A2") (pinfunction "A2_A2") (pintype "input"))
    )
    (net (code "65") (name "INSTR_6_N") (class "Default")
      (node (ref "CMP15") (pin "P$15") (pinfunction "OUT_14_P$15") (pintype "output"))
      (node (ref "CMP28") (pin "P$1") (pinfunction "1_P$1") (pintype "input"))
    )
    (net (code "66") (name "INSTR_7") (class "Default")
      (node (ref "CMP15") (pin "P$8") (pinfunction "OUT_7_P$8") (pintype "output"))
      (node (ref "CMP21") (pin "A3") (pinfunction "A3_A3") (pintype "input"))
      (node (ref "CMP23") (pin "P$1") (pinfunction "A2_P$1") (pintype "input"))
      (node (ref "CMP28") (pin "P$2") (pinfunction "2_P$2") (pintype "input"))
    )
    (net (code "67") (name "INSTR_7_N") (class "Default")
      (node (ref "CMP15") (pin "P$16") (pinfunction "OUT_15_P$16") (pintype "output"))
      (node (ref "CMP31") (pin "4") (pinfunction "3_4") (pintype "input"))
      (node (ref "CMP60") (pin "E") (pinfunction "E_E") (pintype "input"))
    )
    (net (code "68") (name "IS_END") (class "Default")
      (node (ref "CMP10") (pin "P$2") (pinfunction "2_P$2") (pintype "input"))
      (node (ref "CMP31") (pin "OUT_P") (pinfunction "P_OUT_P") (pintype "output"))
      (node (ref "CMP39") (pin "P$3") (pinfunction "3_P$3") (pintype "input"))
      (node (ref "CMP91") (pin "P$11") (pinfunction "IN_10_P$11") (pintype "input"))
    )
    (net (code "69") (name "IS_END_N") (class "Default")
      (node (ref "CMP31") (pin "OUT_M") (pinfunction "N_OUT_M") (pintype "output"))
      (node (ref "CMP91") (pin "P$12") (pinfunction "IN_11_P$12") (pintype "input"))
    )
    (net (code "70") (name "IS_END__SET_A") (class "Default")
      (node (ref "CMP26") (pin "OUT_P") (pinfunction "P_OUT_P") (pintype "output"))
      (node (ref "CMP31") (pin "5") (pinfunction "4_5") (pintype "input"))
    )
    (net (code "71") (name "IS_NOT_INTERRUPTING_END") (class "Default")
      (node (ref "CMP10") (pin "OUT_P") (pinfunction "P_OUT_P") (pintype "output"))
      (node (ref "CMP91") (pin "P$14") (pinfunction "IN_13_P$14") (pintype "input"))
    )
    (net (code "72") (name "IS_SIMPLE_DATA_TRANSFER") (class "Default")
      (node (ref "CMP12") (pin "OUT_P") (pinfunction "P_OUT_P") (pintype "output"))
      (node (ref "CMP26") (pin "P$4") (pinfunction "B1_P$4") (pintype "input"))
      (node (ref "CMP91") (pin "P$13") (pinfunction "IN_12_P$13") (pintype "input"))
    )
    (net (code "73") (name "LDI_X_STATE_0_BYTE_1_WORD") (class "Default")
      (node (ref "CMP9") (pin "OUT_P") (pinfunction "P_OUT_P") (pintype "output"))
      (node (ref "CMP91") (pin "P$9") (pinfunction "IN_8_P$9") (pintype "input"))
    )
    (net (code "74") (name "LOAD_WEIGHT") (class "Default")
      (node (ref "CMP62") (pin "OUT_P") (pinfunction "P_OUT_P") (pintype "output"))
      (node (ref "CMP91") (pin "P$5") (pinfunction "IN_4_P$5") (pintype "input"))
    )
    (net (code "75") (name "MAIN_RN_INPUT_MUX_IS_N") (class "Default")
      (node (ref "CMP49") (pin "P$9") (pinfunction "OUT_8_P$9") (pintype "output"))
    )
    (net (code "76") (name "MAIN_RN_INPUT_MUX_IS_Z") (class "Default")
      (node (ref "CMP49") (pin "P$10") (pinfunction "OUT_9_P$10") (pintype "output"))
    )
    (net (code "77") (name "Net-(CMP1-N)") (class "Default")
      (node (ref "CMP1") (pin "OUT_N") (pinfunction "N_OUT_N") (pintype "output"))
      (node (ref "CMP3") (pin "P$2") (pinfunction "2_P$2") (pintype "input"))
    )
    (net (code "78") (name "Net-(CMP2-N)") (class "Default")
      (node (ref "CMP2") (pin "OUT_N") (pinfunction "N_OUT_N") (pintype "output"))
      (node (ref "CMP3") (pin "P$1") (pinfunction "1_P$1") (pintype "input"))
    )
    (net (code "79") (name "Net-(CMP91-IN_14)") (class "Default")
      (node (ref "CMP91") (pin "P$15") (pinfunction "IN_14_P$15") (pintype "input"))
      (node (ref "CMP91") (pin "P$16") (pinfunction "IN_15_P$16") (pintype "input"))
    )
    (net (code "80") (name "OPCODE_IS_ABS") (class "Default")
      (node (ref "CMP60") (pin "P15") (pinfunction "P15_P15") (pintype "output"))
      (node (ref "CMP81") (pin "P$4") (pinfunction "IN_3_P$4") (pintype "input"))
    )
    (net (code "81") (name "OPCODE_IS_ABSOLUTE_GROUP") (class "Default")
      (node (ref "CMP21") (pin "P11") (pinfunction "P11_P11") (pintype "output"))
      (node (ref "CMP6") (pin "P$5") (pinfunction "IN_4_P$5") (pintype "input"))
    )
    (net (code "82") (name "OPCODE_IS_ADDQ_GROUP") (class "Default")
      (node (ref "CMP21") (pin "P5") (pinfunction "P5_P5") (pintype "output"))
      (node (ref "CMP6") (pin "P$11") (pinfunction "IN_10_P$11") (pintype "input"))
    )
    (net (code "83") (name "OPCODE_IS_ADDX") (class "Default")
      (node (ref "CMP22") (pin "P12") (pinfunction "P12_P12") (pintype "output"))
      (node (ref "CMP7") (pin "P$3") (pinfunction "IN_2_P$3") (pintype "input"))
      (node (ref "CMP74") (pin "P$1") (pinfunction "0_P$1") (pintype "input"))
    )
    (net (code "84") (name "OPCODE_IS_ADD_GROUP") (class "Default")
      (node (ref "CMP21") (pin "P4") (pinfunction "P4_P4") (pintype "output"))
      (node (ref "CMP6") (pin "P$12") (pinfunction "IN_11_P$12") (pintype "input"))
    )
    (net (code "85") (name "OPCODE_IS_ADD_SP") (class "Default")
      (node (ref "CMP22") (pin "P6") (pinfunction "P6_P6") (pintype "output"))
      (node (ref "CMP7") (pin "P$10") (pinfunction "IN_9_P$10") (pintype "input"))
    )
    (net (code "86") (name "OPCODE_IS_AND") (class "Default")
      (node (ref "CMP60") (pin "P1") (pinfunction "P1_P1") (pintype "output"))
    )
    (net (code "87") (name "OPCODE_IS_ANDI_PS") (class "Default")
      (node (ref "CMP22") (pin "P4") (pinfunction "P4_P4") (pintype "output"))
      (node (ref "CMP7") (pin "P$12") (pinfunction "IN_11_P$12") (pintype "input"))
    )
    (net (code "88") (name "OPCODE_IS_AND_GROUP") (class "Default")
      (node (ref "CMP21") (pin "P1") (pinfunction "P1_P1") (pintype "output"))
      (node (ref "CMP6") (pin "P$15") (pinfunction "IN_14_P$15") (pintype "input"))
    )
    (net (code "89") (name "OPCODE_IS_BIT_XX") (class "Default")
      (node (ref "CMP67") (pin "P3") (pinfunction "P3_P3") (pintype "output"))
      (node (ref "CMP8") (pin "P$3") (pinfunction "IN_2_P$3") (pintype "input"))
    )
    (net (code "90") (name "OPCODE_IS_BIT_XX_N") (class "Default")
      (node (ref "CMP67") (pin "N3") (pinfunction "N3_N3") (pintype "output"))
      (node (ref "CMP8") (pin "P$4") (pinfunction "IN_3_P$4") (pintype "input"))
    )
    (net (code "91") (name "OPCODE_IS_BRANCH_GROUP") (class "Default")
      (node (ref "CMP21") (pin "P14") (pinfunction "P14_P14") (pintype "output"))
      (node (ref "CMP6") (pin "P$3") (pinfunction "IN_2_P$3") (pintype "input"))
    )
    (net (code "92") (name "OPCODE_IS_CMP") (class "Default")
      (node (ref "CMP60") (pin "P7") (pinfunction "P7_P7") (pintype "output"))
      (node (ref "CMP81") (pin "P$3") (pinfunction "IN_2_P$3") (pintype "input"))
    )
    (net (code "93") (name "OPCODE_IS_CMP_GROUP") (class "Default")
      (node (ref "CMP21") (pin "P7") (pinfunction "P7_P7") (pintype "output"))
      (node (ref "CMP6") (pin "P$9") (pinfunction "IN_8_P$9") (pintype "input"))
    )
    (net (code "94") (name "OPCODE_IS_DIV") (class "Default")
      (node (ref "CMP38") (pin "P$2") (pinfunction "2_P$2") (pintype "input"))
      (node (ref "CMP7") (pin "P$4") (pinfunction "IN_3_P$4") (pintype "input"))
      (node (ref "CMP76") (pin "OUT_P") (pinfunction "P_OUT_P") (pintype "output"))
      (node (ref "CMP77") (pin "P$1") (pinfunction "0_P$1") (pintype "input"))
    )
    (net (code "95") (name "OPCODE_IS_DIVS") (class "Default")
      (node (ref "CMP22") (pin "P11") (pinfunction "P11_P11") (pintype "output"))
      (node (ref "CMP7") (pin "P$5") (pinfunction "IN_4_P$5") (pintype "input"))
      (node (ref "CMP76") (pin "P$2") (pinfunction "A1_P$2") (pintype "input"))
    )
    (net (code "96") (name "OPCODE_IS_DIVU") (class "Default")
      (node (ref "CMP22") (pin "P10") (pinfunction "P10_P10") (pintype "output"))
      (node (ref "CMP76") (pin "P$1") (pinfunction "A2_P$1") (pintype "input"))
    )
    (net (code "97") (name "OPCODE_IS_IMMEDIATE_GROUP") (class "Default")
      (node (ref "CMP21") (pin "P13") (pinfunction "P13_P13") (pintype "output"))
      (node (ref "CMP67") (pin "E") (pinfunction "E_E") (pintype "input"))
      (node (ref "CMP69") (pin "P$2") (pinfunction "2_P$2") (pintype "input"))
      (node (ref "CMP72") (pin "P$2") (pinfunction "2_P$2") (pintype "input"))
    )
    (net (code "98") (name "OPCODE_IS_INDIRECT_GROUP") (class "Default")
      (node (ref "CMP21") (pin "P8") (pinfunction "P8_P8") (pintype "output"))
      (node (ref "CMP36") (pin "P$1") (pinfunction "A2_P$1") (pintype "input"))
      (node (ref "CMP6") (pin "P$8") (pinfunction "IN_7_P$8") (pintype "input"))
    )
    (net (code "99") (name "OPCODE_IS_INDIRECT_POSTINC") (class "Default")
      (node (ref "CMP12") (pin "3") (pinfunction "2_3") (pintype "input"))
      (node (ref "CMP36") (pin "OUT_P") (pinfunction "P_OUT_P") (pintype "output"))
      (node (ref "CMP6") (pin "P$1") (pinfunction "IN_0_P$1") (pintype "input"))
    )
    (net (code "100") (name "OPCODE_IS_INV") (class "Default")
      (node (ref "CMP60") (pin "P11") (pinfunction "P11_P11") (pintype "output"))
      (node (ref "CMP81") (pin "P$8") (pinfunction "IN_7_P$8") (pintype "input"))
    )
    (net (code "101") (name "OPCODE_IS_JMP_ABS") (class "Default")
      (node (ref "CMP22") (pin "P3") (pinfunction "P3_P3") (pintype "output"))
      (node (ref "CMP7") (pin "P$13") (pinfunction "IN_12_P$13") (pintype "input"))
    )
    (net (code "102") (name "OPCODE_IS_JMP_R0") (class "Default")
      (node (ref "CMP22") (pin "P2") (pinfunction "P2_P2") (pintype "output"))
      (node (ref "CMP7") (pin "P$14") (pinfunction "IN_13_P$14") (pintype "input"))
    )
    (net (code "103") (name "OPCODE_IS_JSR_ABS") (class "Default")
      (node (ref "CMP5") (pin "P$1") (pinfunction "A2_P$1") (pintype "input"))
      (node (ref "CMP59") (pin "P15") (pinfunction "P15_P15") (pintype "output"))
      (node (ref "CMP8") (pin "P$10") (pinfunction "IN_9_P$10") (pintype "input"))
    )
    (net (code "104") (name "OPCODE_IS_JSR_R0") (class "Default")
      (node (ref "CMP5") (pin "P$2") (pinfunction "A1_P$2") (pintype "input"))
      (node (ref "CMP59") (pin "P14") (pinfunction "P14_P14") (pintype "output"))
      (node (ref "CMP8") (pin "P$11") (pinfunction "IN_10_P$11") (pintype "input"))
    )
    (net (code "105") (name "OPCODE_IS_JSR_X") (class "Default")
      (node (ref "CMP5") (pin "OUT_P") (pinfunction "P_OUT_P") (pintype "output"))
      (node (ref "CMP91") (pin "P$10") (pinfunction "IN_9_P$10") (pintype "input"))
    )
    (net (code "106") (name "OPCODE_IS_LDI_X") (class "Default")
      (node (ref "CMP29") (pin "1") (pinfunction "0_1") (pintype "input"))
      (node (ref "CMP69") (pin "OUT_P") (pinfunction "P_OUT_P") (pintype "output"))
      (node (ref "CMP8") (pin "P$1") (pinfunction "IN_0_P$1") (pintype "input"))
      (node (ref "CMP9") (pin "P$2") (pinfunction "A1_P$2") (pintype "input"))
      (node (ref "CMP9") (pin "P$4") (pinfunction "B0_P$4") (pintype "input"))
    )
    (net (code "107") (name "OPCODE_IS_LD_ST") (class "Default")
      (node (ref "CMP29") (pin "OUT_P") (pinfunction "P_OUT_P") (pintype "output"))
      (node (ref "CMP91") (pin "P$8") (pinfunction "IN_7_P$8") (pintype "input"))
    )
    (net (code "108") (name "OPCODE_IS_LD_ST_SIMPLE") (class "Default")
      (node (ref "CMP28") (pin "OUT_P") (pinfunction "P_OUT_P") (pintype "output"))
      (node (ref "CMP29") (pin "3") (pinfunction "2_3") (pintype "input"))
    )
    (net (code "109") (name "OPCODE_IS_LOGIC_GROUP") (class "Default")
      (node (ref "CMP23") (pin "OUT_M") (pinfunction "N_OUT_M") (pintype "output"))
      (node (ref "CMP6") (pin "P$2") (pinfunction "IN_1_P$2") (pintype "input"))
    )
    (net (code "110") (name "OPCODE_IS_MISC_GROUP") (class "Default")
      (node (ref "CMP21") (pin "P15") (pinfunction "P15_P15") (pintype "output"))
      (node (ref "CMP22") (pin "E") (pinfunction "E_E") (pintype "input"))
    )
    (net (code "111") (name "OPCODE_IS_MOVER") (class "Default")
      (node (ref "CMP60") (pin "P0") (pinfunction "P0_P0") (pintype "output"))
      (node (ref "CMP81") (pin "P$10") (pinfunction "IN_9_P$10") (pintype "input"))
    )
    (net (code "112") (name "OPCODE_IS_MOVER_GROUP") (class "Default")
      (node (ref "CMP21") (pin "P0") (pinfunction "P0_P0") (pintype "output"))
    )
    (net (code "113") (name "OPCODE_IS_MOVE_R0_SP") (class "Default")
      (node (ref "CMP22") (pin "P0") (pinfunction "P0_P0") (pintype "output"))
      (node (ref "CMP7") (pin "P$16") (pinfunction "IN_15_P$16") (pintype "input"))
    )
    (net (code "114") (name "OPCODE_IS_MOVE_SP_R0") (class "Default")
      (node (ref "CMP22") (pin "P1") (pinfunction "P1_P1") (pintype "output"))
      (node (ref "CMP7") (pin "P$15") (pinfunction "IN_14_P$15") (pintype "input"))
    )
    (net (code "115") (name "OPCODE_IS_MUL") (class "Default")
      (node (ref "CMP75") (pin "OUT_P") (pinfunction "P_OUT_P") (pintype "output"))
      (node (ref "CMP77") (pin "P$3") (pinfunction "2_P$3") (pintype "input"))
    )
    (net (code "116") (name "OPCODE_IS_MULS") (class "Default")
      (node (ref "CMP22") (pin "P9") (pinfunction "P9_P9") (pintype "output"))
      (node (ref "CMP7") (pin "P$8") (pinfunction "IN_7_P$8") (pintype "input"))
      (node (ref "CMP75") (pin "P$2") (pinfunction "A1_P$2") (pintype "input"))
    )
    (net (code "117") (name "OPCODE_IS_MULU") (class "Default")
      (node (ref "CMP22") (pin "P8") (pinfunction "P8_P8") (pintype "output"))
      (node (ref "CMP7") (pin "P$7") (pinfunction "IN_6_P$7") (pintype "input"))
      (node (ref "CMP75") (pin "P$1") (pinfunction "A2_P$1") (pintype "input"))
    )
    (net (code "118") (name "OPCODE_IS_MUL_N") (class "Default")
      (node (ref "CMP7") (pin "P$6") (pinfunction "IN_5_P$6") (pintype "input"))
      (node (ref "CMP75") (pin "OUT_M") (pinfunction "N_OUT_M") (pintype "output"))
    )
    (net (code "119") (name "OPCODE_IS_MUL_SQRT_DIV") (class "Default")
      (node (ref "CMP77") (pin "OUT_P") (pinfunction "P_OUT_P") (pintype "output"))
      (node (ref "CMP81") (pin "P$1") (pinfunction "IN_0_P$1") (pintype "input"))
    )
    (net (code "120") (name "OPCODE_IS_NEG") (class "Default")
      (node (ref "CMP60") (pin "P14") (pinfunction "P14_P14") (pintype "output"))
      (node (ref "CMP81") (pin "P$6") (pinfunction "IN_5_P$6") (pintype "input"))
    )
    (net (code "121") (name "OPCODE_IS_NEGX") (class "Default")
      (node (ref "CMP22") (pin "P14") (pinfunction "P14_P14") (pintype "output"))
      (node (ref "CMP7") (pin "P$1") (pinfunction "IN_0_P$1") (pintype "input"))
      (node (ref "CMP74") (pin "P$3") (pinfunction "2_P$3") (pintype "input"))
    )
    (net (code "122") (name "OPCODE_IS_NOP") (class "Default")
      (node (ref "CMP31") (pin "2") (pinfunction "1_2") (pintype "input"))
      (node (ref "CMP4") (pin "OUT_P") (pinfunction "P_OUT_P") (pintype "output"))
      (node (ref "CMP81") (pin "P$14") (pinfunction "IN_13_P$14") (pintype "input"))
    )
    (net (code "123") (name "OPCODE_IS_NOP_1") (class "Default")
      (node (ref "CMP22") (pin "P15") (pinfunction "P15_P15") (pintype "output"))
      (node (ref "CMP4") (pin "P$2") (pinfunction "A1_P$2") (pintype "input"))
    )
    (net (code "124") (name "OPCODE_IS_NOP_2") (class "Default")
      (node (ref "CMP4") (pin "P$1") (pinfunction "A2_P$1") (pintype "input"))
      (node (ref "CMP59") (pin "P5") (pinfunction "P5_P5") (pintype "output"))
    )
    (net (code "125") (name "OPCODE_IS_OR") (class "Default")
      (node (ref "CMP60") (pin "P3") (pinfunction "P3_P3") (pintype "output"))
      (node (ref "CMP81") (pin "P$7") (pinfunction "IN_6_P$7") (pintype "input"))
    )
    (net (code "126") (name "OPCODE_IS_ORI_PS") (class "Default")
      (node (ref "CMP22") (pin "P5") (pinfunction "P5_P5") (pintype "output"))
      (node (ref "CMP7") (pin "P$11") (pinfunction "IN_10_P$11") (pintype "input"))
    )
    (net (code "127") (name "OPCODE_IS_OR_GROUP") (class "Default")
      (node (ref "CMP21") (pin "P3") (pinfunction "P3_P3") (pintype "output"))
      (node (ref "CMP6") (pin "P$13") (pinfunction "IN_12_P$13") (pintype "input"))
    )
    (net (code "128") (name "OPCODE_IS_POP_PS") (class "Default")
      (node (ref "CMP12") (pin "4") (pinfunction "3_4") (pintype "input"))
      (node (ref "CMP59") (pin "P4") (pinfunction "P4_P4") (pintype "output"))
      (node (ref "CMP8") (pin "P$16") (pinfunction "IN_15_P$16") (pintype "input"))
    )
    (net (code "129") (name "OPCODE_IS_POP_RA") (class "Default")
      (node (ref "CMP12") (pin "2") (pinfunction "1_2") (pintype "input"))
      (node (ref "CMP29") (pin "4") (pinfunction "3_4") (pintype "input"))
      (node (ref "CMP81") (pin "P$15") (pinfunction "IN_14_P$15") (pintype "input"))
      (node (ref "CMP94") (pin "P0") (pinfunction "P0_P0") (pintype "output"))
    )
    (net (code "130") (name "OPCODE_IS_POSTINC_GROUP") (class "Default")
      (node (ref "CMP21") (pin "P9") (pinfunction "P9_P9") (pintype "output"))
      (node (ref "CMP36") (pin "P$2") (pinfunction "A1_P$2") (pintype "input"))
      (node (ref "CMP6") (pin "P$7") (pinfunction "IN_6_P$7") (pintype "input"))
    )
    (net (code "131") (name "OPCODE_IS_PUSH_PS") (class "Default")
      (node (ref "CMP12") (pin "5") (pinfunction "4_5") (pintype "input"))
      (node (ref "CMP59") (pin "P12") (pinfunction "P12_P12") (pintype "output"))
      (node (ref "CMP8") (pin "P$13") (pinfunction "IN_12_P$13") (pintype "input"))
    )
    (net (code "132") (name "OPCODE_IS_PUSH_RA") (class "Default")
      (node (ref "CMP12") (pin "1") (pinfunction "0_1") (pintype "input"))
      (node (ref "CMP29") (pin "2") (pinfunction "1_2") (pintype "input"))
      (node (ref "CMP81") (pin "P$16") (pinfunction "IN_15_P$16") (pintype "input"))
      (node (ref "CMP94") (pin "P2") (pinfunction "P2_P2") (pintype "output"))
    )
    (net (code "133") (name "OPCODE_IS_RET") (class "Default")
      (node (ref "CMP59") (pin "P6") (pinfunction "P6_P6") (pintype "output"))
      (node (ref "CMP8") (pin "P$15") (pinfunction "IN_14_P$15") (pintype "input"))
    )
    (net (code "134") (name "OPCODE_IS_RETI") (class "Default")
      (node (ref "CMP59") (pin "P7") (pinfunction "P7_P7") (pintype "output"))
      (node (ref "CMP8") (pin "P$14") (pinfunction "IN_13_P$14") (pintype "input"))
    )
    (net (code "135") (name "OPCODE_IS_SHIFT_BIT") (class "Default")
      (node (ref "CMP72") (pin "OUT_P") (pinfunction "P_OUT_P") (pintype "output"))
      (node (ref "CMP8") (pin "P$5") (pinfunction "IN_4_P$5") (pintype "input"))
    )
    (net (code "136") (name "OPCODE_IS_SHIFT_XX") (class "Default")
      (node (ref "CMP24") (pin "P$2") (pinfunction "2_P$2") (pintype "input"))
      (node (ref "CMP62") (pin "P$2") (pinfunction "1_P$2") (pintype "input"))
      (node (ref "CMP67") (pin "P2") (pinfunction "P2_P2") (pintype "output"))
      (node (ref "CMP8") (pin "P$2") (pinfunction "IN_1_P$2") (pintype "input"))
    )
    (net (code "137") (name "OPCODE_IS_SQRT") (class "Default")
      (node (ref "CMP22") (pin "P7") (pinfunction "P7_P7") (pintype "output"))
      (node (ref "CMP7") (pin "P$9") (pinfunction "IN_8_P$9") (pintype "input"))
      (node (ref "CMP77") (pin "P$2") (pinfunction "1_P$2") (pintype "input"))
    )
    (net (code "138") (name "OPCODE_IS_STACK_GROUP") (class "Default")
      (node (ref "CMP21") (pin "P12") (pinfunction "P12_P12") (pintype "output"))
      (node (ref "CMP59") (pin "E") (pinfunction "E_E") (pintype "input"))
      (node (ref "CMP6") (pin "P$4") (pinfunction "IN_3_P$4") (pintype "input"))
      (node (ref "CMP94") (pin "E") (pinfunction "E_E") (pintype "input"))
    )
    (net (code "139") (name "OPCODE_IS_STACK_REL_GROUP") (class "Default")
      (node (ref "CMP21") (pin "P10") (pinfunction "P10_P10") (pintype "output"))
      (node (ref "CMP26") (pin "P$1") (pinfunction "A0_P$1") (pintype "input"))
      (node (ref "CMP6") (pin "P$6") (pinfunction "IN_5_P$6") (pintype "input"))
    )
    (net (code "140") (name "OPCODE_IS_SUB") (class "Default")
      (node (ref "CMP60") (pin "P6") (pinfunction "P6_P6") (pintype "output"))
      (node (ref "CMP81") (pin "P$5") (pinfunction "IN_4_P$5") (pintype "input"))
    )
    (net (code "141") (name "OPCODE_IS_SUBX") (class "Default")
      (node (ref "CMP22") (pin "P13") (pinfunction "P13_P13") (pintype "output"))
      (node (ref "CMP7") (pin "P$2") (pinfunction "IN_1_P$2") (pintype "input"))
      (node (ref "CMP74") (pin "P$2") (pinfunction "1_P$2") (pintype "input"))
    )
    (net (code "142") (name "OPCODE_IS_SUB_GROUP") (class "Default")
      (node (ref "CMP21") (pin "P6") (pinfunction "P6_P6") (pintype "output"))
      (node (ref "CMP6") (pin "P$10") (pinfunction "IN_9_P$10") (pintype "input"))
    )
    (net (code "143") (name "OPCODE_IS_SXT") (class "Default")
      (node (ref "CMP60") (pin "P8") (pinfunction "P8_P8") (pintype "output"))
      (node (ref "CMP81") (pin "P$11") (pinfunction "IN_10_P$11") (pintype "input"))
    )
    (net (code "144") (name "OPCODE_IS_TEST") (class "Default")
      (node (ref "CMP60") (pin "P9") (pinfunction "P9_P9") (pintype "output"))
      (node (ref "CMP81") (pin "P$9") (pinfunction "IN_8_P$9") (pintype "input"))
    )
    (net (code "145") (name "OPCODE_IS_TRAP") (class "Default")
      (node (ref "CMP27") (pin "P$2") (pinfunction "2_P$2") (pintype "input"))
      (node (ref "CMP59") (pin "P13") (pinfunction "P13_P13") (pintype "output"))
      (node (ref "CMP8") (pin "P$12") (pinfunction "IN_11_P$12") (pintype "input"))
    )
    (net (code "146") (name "OPCODE_IS_XOR_GROUP") (class "Default")
      (node (ref "CMP21") (pin "P2") (pinfunction "P2_P2") (pintype "output"))
      (node (ref "CMP6") (pin "P$14") (pinfunction "IN_13_P$14") (pintype "input"))
    )
    (net (code "147") (name "OPCODE_IS_X_ARITH") (class "Default")
      (node (ref "CMP31") (pin "3") (pinfunction "2_3") (pintype "input"))
      (node (ref "CMP74") (pin "OUT_P") (pinfunction "P_OUT_P") (pintype "output"))
      (node (ref "CMP81") (pin "P$2") (pinfunction "IN_1_P$2") (pintype "input"))
    )
    (net (code "148") (name "R0_IS_N") (class "Default")
      (node (ref "CMP49") (pin "P$1") (pinfunction "OUT_0_P$1") (pintype "output"))
    )
    (net (code "149") (name "R0_IS_Z") (class "Default")
      (node (ref "CMP49") (pin "P$5") (pinfunction "OUT_4_P$5") (pintype "output"))
    )
    (net (code "150") (name "R1_IS_N") (class "Default")
      (node (ref "CMP49") (pin "P$2") (pinfunction "OUT_1_P$2") (pintype "output"))
    )
    (net (code "151") (name "R1_IS_Z") (class "Default")
      (node (ref "CMP38") (pin "P$1") (pinfunction "1_P$1") (pintype "input"))
      (node (ref "CMP49") (pin "P$6") (pinfunction "OUT_5_P$6") (pintype "output"))
    )
    (net (code "152") (name "R2_IS_N") (class "Default")
      (node (ref "CMP49") (pin "P$3") (pinfunction "OUT_2_P$3") (pintype "output"))
    )
    (net (code "153") (name "R2_IS_Z") (class "Default")
      (node (ref "CMP49") (pin "P$7") (pinfunction "OUT_6_P$7") (pintype "output"))
    )
    (net (code "154") (name "R3_IS_N") (class "Default")
      (node (ref "CMP49") (pin "P$4") (pinfunction "OUT_3_P$4") (pintype "output"))
    )
    (net (code "155") (name "R3_IS_Z") (class "Default")
      (node (ref "CMP49") (pin "P$8") (pinfunction "OUT_7_P$8") (pintype "output"))
    )
    (net (code "156") (name "RA_EQUALS_RB") (class "Default")
      (node (ref "CMP3") (pin "OUT_P") (pinfunction "P_OUT_P") (pintype "output"))
      (node (ref "CMP60") (pin "A3") (pinfunction "A3_A3") (pintype "input"))
    )
    (net (code "157") (name "RA_EQUALS_RB_N") (class "Default")
      (node (ref "CMP3") (pin "OUT_M") (pinfunction "N_OUT_M") (pintype "output"))
    )
    (net (code "158") (name "SHIFT_IS_SHIFTING") (class "Default")
      (node (ref "CMP24") (pin "OUT_P") (pinfunction "P_OUT_P") (pintype "output"))
      (node (ref "CMP91") (pin "P$4") (pinfunction "IN_3_P$4") (pintype "input"))
    )
    (net (code "159") (name "SHIFT_VAL_NON_ZERO") (class "Default")
      (node (ref "CMP20") (pin "OUT_P") (pinfunction "P_OUT_P") (pintype "output"))
      (node (ref "CMP24") (pin "P$3") (pinfunction "3_P$3") (pintype "input"))
      (node (ref "CMP91") (pin "P$1") (pinfunction "IN_0_P$1") (pintype "input"))
    )
    (net (code "160") (name "SHIFT_VAL_NON_ZERO_N") (class "Default")
      (node (ref "CMP20") (pin "OUT_M") (pinfunction "N_OUT_M") (pintype "output"))
      (node (ref "CMP62") (pin "P$4") (pinfunction "3_P$4") (pintype "input"))
      (node (ref "CMP91") (pin "P$2") (pinfunction "IN_1_P$2") (pintype "input"))
    )
    (net (code "161") (name "STATE_0") (class "Default")
      (node (ref "CMP13") (pin "P$1") (pinfunction "OUT_0_P$1") (pintype "output"))
      (node (ref "CMP9") (pin "P$6") (pinfunction "B2_P$6") (pintype "input"))
    )
    (net (code "162") (name "STATE_1") (class "Default")
      (node (ref "CMP13") (pin "P$2") (pinfunction "OUT_1_P$2") (pintype "output"))
      (node (ref "CMP9") (pin "P$3") (pinfunction "A2_P$3") (pintype "input"))
    )
    (net (code "163") (name "STATE_2") (class "Default")
      (node (ref "CMP13") (pin "P$3") (pinfunction "OUT_2_P$3") (pintype "output"))
      (node (ref "CMP24") (pin "P$1") (pinfunction "1_P$1") (pintype "input"))
      (node (ref "CMP62") (pin "P$1") (pinfunction "0_P$1") (pintype "input"))
    )
    (net (code "164") (name "STATE_3") (class "Default")
      (node (ref "CMP13") (pin "P$4") (pinfunction "OUT_3_P$4") (pintype "output"))
      (node (ref "CMP31") (pin "1") (pinfunction "0_1") (pintype "input"))
    )
    (net (code "165") (name "STATE_4") (class "Default")
      (node (ref "CMP13") (pin "P$5") (pinfunction "OUT_4_P$5") (pintype "output"))
    )
    (net (code "166") (name "STATE_5") (class "Default")
      (node (ref "CMP13") (pin "P$6") (pinfunction "OUT_5_P$6") (pintype "output"))
      (node (ref "CMP25") (pin "P$1") (pinfunction "A2_P$1") (pintype "input"))
    )
    (net (code "167") (name "STATE_6") (class "Default")
      (node (ref "CMP13") (pin "P$7") (pinfunction "OUT_6_P$7") (pintype "output"))
    )
    (net (code "168") (name "STATE_7") (class "Default")
      (node (ref "CMP13") (pin "P$8") (pinfunction "OUT_7_P$8") (pintype "output"))
      (node (ref "CMP25") (pin "P$2") (pinfunction "A1_P$2") (pintype "input"))
      (node (ref "CMP27") (pin "P$1") (pinfunction "1_P$1") (pintype "input"))
    )
    (net (code "169") (name "STATE_8") (class "Default")
      (node (ref "CMP13") (pin "P$9") (pinfunction "OUT_8_P$9") (pintype "output"))
    )
    (net (code "170") (name "STATE_9") (class "Default")
      (node (ref "CMP13") (pin "P$10") (pinfunction "OUT_9_P$10") (pintype "output"))
    )
    (net (code "171") (name "STATE_10") (class "Default")
      (node (ref "CMP13") (pin "P$11") (pinfunction "OUT_10_P$11") (pintype "output"))
    )
    (net (code "172") (name "STATE_11") (class "Default")
      (node (ref "CMP13") (pin "P$12") (pinfunction "OUT_11_P$12") (pintype "output"))
    )
    (net (code "173") (name "STATE_12") (class "Default")
      (node (ref "CMP13") (pin "P$13") (pinfunction "OUT_12_P$13") (pintype "output"))
    )
    (net (code "174") (name "STATE_13") (class "Default")
      (node (ref "CMP13") (pin "P$14") (pinfunction "OUT_13_P$14") (pintype "output"))
    )
    (net (code "175") (name "STATE_14") (class "Default")
      (node (ref "CMP13") (pin "P$15") (pinfunction "OUT_14_P$15") (pintype "output"))
    )
    (net (code "176") (name "STATE_15") (class "Default")
      (node (ref "CMP13") (pin "P$16") (pinfunction "OUT_15_P$16") (pintype "output"))
    )
    (net (code "177") (name "TAKE_INTERRUPT") (class "Default")
      (node (ref "CMP39") (pin "OUT_P") (pinfunction "P_OUT_P") (pintype "output"))
      (node (ref "CMP91") (pin "P$7") (pinfunction "IN_6_P$7") (pintype "input"))
    )
    (net (code "178") (name "TAKE_INTERRUPT_N") (class "Default")
      (node (ref "CMP10") (pin "P$1") (pinfunction "1_P$1") (pintype "input"))
      (node (ref "CMP39") (pin "OUT_M") (pinfunction "M_OUT_M") (pintype "output"))
    )
    (net (code "179") (name "TRAP_STATE_7") (class "Default")
      (node (ref "CMP27") (pin "OUT_P") (pinfunction "P_OUT_P") (pintype "output"))
      (node (ref "CMP91") (pin "P$6") (pinfunction "IN_5_P$6") (pintype "input"))
    )
    (net (code "180") (name "unconnected-(CMP1-P-PadOUT_P)") (class "Default")
      (node (ref "CMP1") (pin "OUT_P") (pinfunction "P_OUT_P") (pintype "output"))
    )
    (net (code "181") (name "unconnected-(CMP2-P-PadOUT_P)") (class "Default")
      (node (ref "CMP2") (pin "OUT_P") (pinfunction "P_OUT_P") (pintype "output"))
    )
    (net (code "182") (name "unconnected-(CMP4-N-PadOUT_M)") (class "Default")
      (node (ref "CMP4") (pin "OUT_M") (pinfunction "N_OUT_M") (pintype "output"))
    )
    (net (code "183") (name "unconnected-(CMP5-N-PadOUT_M)") (class "Default")
      (node (ref "CMP5") (pin "OUT_M") (pinfunction "N_OUT_M") (pintype "output"))
    )
    (net (code "184") (name "unconnected-(CMP6-IN_15-PadP$16)") (class "Default")
      (node (ref "CMP6") (pin "P$16") (pinfunction "IN_15_P$16") (pintype "input"))
    )
    (net (code "185") (name "unconnected-(CMP6-OUT-PadINPUT)") (class "Default")
      (node (ref "CMP6") (pin "INPUT") (pinfunction "OUT_INPUT") (pintype "output"))
    )
    (net (code "186") (name "unconnected-(CMP7-OUT-PadINPUT)") (class "Default")
      (node (ref "CMP7") (pin "INPUT") (pinfunction "OUT_INPUT") (pintype "output"))
    )
    (net (code "187") (name "unconnected-(CMP9-N-PadOUT_M)") (class "Default")
      (node (ref "CMP9") (pin "OUT_M") (pinfunction "N_OUT_M") (pintype "output"))
    )
    (net (code "188") (name "unconnected-(CMP10-N-PadOUT_M)") (class "Default")
      (node (ref "CMP10") (pin "OUT_M") (pinfunction "N_OUT_M") (pintype "output"))
    )
    (net (code "189") (name "unconnected-(CMP12-N-PadOUT_M)") (class "Default")
      (node (ref "CMP12") (pin "OUT_M") (pinfunction "N_OUT_M") (pintype "output"))
    )
    (net (code "190") (name "unconnected-(CMP17-OUT_7-PadP$8)") (class "Default")
      (node (ref "CMP17") (pin "P$8") (pinfunction "OUT_7_P$8") (pintype "output"))
    )
    (net (code "191") (name "unconnected-(CMP17-OUT_15-PadP$16)") (class "Default")
      (node (ref "CMP17") (pin "P$16") (pinfunction "OUT_15_P$16") (pintype "output"))
    )
    (net (code "192") (name "unconnected-(CMP21-PadE)") (class "Default")
      (node (ref "CMP21") (pin "E") (pinfunction "E_E") (pintype "input"))
    )
    (net (code "193") (name "unconnected-(CMP21-PadN0)") (class "Default")
      (node (ref "CMP21") (pin "N0") (pinfunction "N0_N0") (pintype "output"))
    )
    (net (code "194") (name "unconnected-(CMP21-PadN1)") (class "Default")
      (node (ref "CMP21") (pin "N1") (pinfunction "N1_N1") (pintype "output"))
    )
    (net (code "195") (name "unconnected-(CMP21-PadN2)") (class "Default")
      (node (ref "CMP21") (pin "N2") (pinfunction "N2_N2") (pintype "output"))
    )
    (net (code "196") (name "unconnected-(CMP21-PadN3)") (class "Default")
      (node (ref "CMP21") (pin "N3") (pinfunction "N3_N3") (pintype "output"))
    )
    (net (code "197") (name "unconnected-(CMP21-PadN4)") (class "Default")
      (node (ref "CMP21") (pin "N4") (pinfunction "N4_N4") (pintype "output"))
    )
    (net (code "198") (name "unconnected-(CMP21-PadN5)") (class "Default")
      (node (ref "CMP21") (pin "N5") (pinfunction "N5_N5") (pintype "output"))
    )
    (net (code "199") (name "unconnected-(CMP21-PadN6)") (class "Default")
      (node (ref "CMP21") (pin "N6") (pinfunction "N6_N6") (pintype "output"))
    )
    (net (code "200") (name "unconnected-(CMP21-PadN7)") (class "Default")
      (node (ref "CMP21") (pin "N7") (pinfunction "N7_N7") (pintype "output"))
    )
    (net (code "201") (name "unconnected-(CMP21-PadN8)") (class "Default")
      (node (ref "CMP21") (pin "N8") (pinfunction "N8_N8") (pintype "output"))
    )
    (net (code "202") (name "unconnected-(CMP21-PadN9)") (class "Default")
      (node (ref "CMP21") (pin "N9") (pinfunction "N9_N9") (pintype "output"))
    )
    (net (code "203") (name "unconnected-(CMP21-PadN10)") (class "Default")
      (node (ref "CMP21") (pin "N10") (pinfunction "N10_N10") (pintype "output"))
    )
    (net (code "204") (name "unconnected-(CMP21-PadN11)") (class "Default")
      (node (ref "CMP21") (pin "N11") (pinfunction "N11_N11") (pintype "output"))
    )
    (net (code "205") (name "unconnected-(CMP21-PadN12)") (class "Default")
      (node (ref "CMP21") (pin "N12") (pinfunction "N12_N12") (pintype "output"))
    )
    (net (code "206") (name "unconnected-(CMP21-PadN13)") (class "Default")
      (node (ref "CMP21") (pin "N13") (pinfunction "N13_N13") (pintype "output"))
    )
    (net (code "207") (name "unconnected-(CMP21-PadN14)") (class "Default")
      (node (ref "CMP21") (pin "N14") (pinfunction "N14_N14") (pintype "output"))
    )
    (net (code "208") (name "unconnected-(CMP21-PadN15)") (class "Default")
      (node (ref "CMP21") (pin "N15") (pinfunction "N15_N15") (pintype "output"))
    )
    (net (code "209") (name "unconnected-(CMP22-PadN0)") (class "Default")
      (node (ref "CMP22") (pin "N0") (pinfunction "N0_N0") (pintype "output"))
    )
    (net (code "210") (name "unconnected-(CMP22-PadN1)") (class "Default")
      (node (ref "CMP22") (pin "N1") (pinfunction "N1_N1") (pintype "output"))
    )
    (net (code "211") (name "unconnected-(CMP22-PadN2)") (class "Default")
      (node (ref "CMP22") (pin "N2") (pinfunction "N2_N2") (pintype "output"))
    )
    (net (code "212") (name "unconnected-(CMP22-PadN3)") (class "Default")
      (node (ref "CMP22") (pin "N3") (pinfunction "N3_N3") (pintype "output"))
    )
    (net (code "213") (name "unconnected-(CMP22-PadN4)") (class "Default")
      (node (ref "CMP22") (pin "N4") (pinfunction "N4_N4") (pintype "output"))
    )
    (net (code "214") (name "unconnected-(CMP22-PadN5)") (class "Default")
      (node (ref "CMP22") (pin "N5") (pinfunction "N5_N5") (pintype "output"))
    )
    (net (code "215") (name "unconnected-(CMP22-PadN6)") (class "Default")
      (node (ref "CMP22") (pin "N6") (pinfunction "N6_N6") (pintype "output"))
    )
    (net (code "216") (name "unconnected-(CMP22-PadN7)") (class "Default")
      (node (ref "CMP22") (pin "N7") (pinfunction "N7_N7") (pintype "output"))
    )
    (net (code "217") (name "unconnected-(CMP22-PadN8)") (class "Default")
      (node (ref "CMP22") (pin "N8") (pinfunction "N8_N8") (pintype "output"))
    )
    (net (code "218") (name "unconnected-(CMP22-PadN9)") (class "Default")
      (node (ref "CMP22") (pin "N9") (pinfunction "N9_N9") (pintype "output"))
    )
    (net (code "219") (name "unconnected-(CMP22-PadN10)") (class "Default")
      (node (ref "CMP22") (pin "N10") (pinfunction "N10_N10") (pintype "output"))
    )
    (net (code "220") (name "unconnected-(CMP22-PadN11)") (class "Default")
      (node (ref "CMP22") (pin "N11") (pinfunction "N11_N11") (pintype "output"))
    )
    (net (code "221") (name "unconnected-(CMP22-PadN12)") (class "Default")
      (node (ref "CMP22") (pin "N12") (pinfunction "N12_N12") (pintype "output"))
    )
    (net (code "222") (name "unconnected-(CMP22-PadN13)") (class "Default")
      (node (ref "CMP22") (pin "N13") (pinfunction "N13_N13") (pintype "output"))
    )
    (net (code "223") (name "unconnected-(CMP22-PadN14)") (class "Default")
      (node (ref "CMP22") (pin "N14") (pinfunction "N14_N14") (pintype "output"))
    )
    (net (code "224") (name "unconnected-(CMP22-PadN15)") (class "Default")
      (node (ref "CMP22") (pin "N15") (pinfunction "N15_N15") (pintype "output"))
    )
    (net (code "225") (name "unconnected-(CMP23-P-PadOUT_P)") (class "Default")
      (node (ref "CMP23") (pin "OUT_P") (pinfunction "P_OUT_P") (pintype "output"))
    )
    (net (code "226") (name "unconnected-(CMP24-M-PadOUT_M)") (class "Default")
      (node (ref "CMP24") (pin "OUT_M") (pinfunction "M_OUT_M") (pintype "output"))
    )
    (net (code "227") (name "unconnected-(CMP25-N-PadOUT_M)") (class "Default")
      (node (ref "CMP25") (pin "OUT_M") (pinfunction "N_OUT_M") (pintype "output"))
    )
    (net (code "228") (name "unconnected-(CMP26-N-PadOUT_M)") (class "Default")
      (node (ref "CMP26") (pin "OUT_M") (pinfunction "N_OUT_M") (pintype "output"))
    )
    (net (code "229") (name "unconnected-(CMP27-N-PadOUT_M)") (class "Default")
      (node (ref "CMP27") (pin "OUT_M") (pinfunction "N_OUT_M") (pintype "output"))
    )
    (net (code "230") (name "unconnected-(CMP28-N-PadOUT_M)") (class "Default")
      (node (ref "CMP28") (pin "OUT_M") (pinfunction "N_OUT_M") (pintype "output"))
    )
    (net (code "231") (name "unconnected-(CMP29-N-PadOUT_M)") (class "Default")
      (node (ref "CMP29") (pin "OUT_M") (pinfunction "N_OUT_M") (pintype "output"))
    )
    (net (code "232") (name "unconnected-(CMP30-N-PadOUT_M)") (class "Default")
      (node (ref "CMP30") (pin "OUT_M") (pinfunction "N_OUT_M") (pintype "output"))
    )
    (net (code "233") (name "unconnected-(CMP36-N-PadOUT_M)") (class "Default")
      (node (ref "CMP36") (pin "OUT_M") (pinfunction "N_OUT_M") (pintype "output"))
    )
    (net (code "234") (name "unconnected-(CMP49-OUT_12-PadP$13)") (class "Default")
      (node (ref "CMP49") (pin "P$13") (pinfunction "OUT_12_P$13") (pintype "output"))
    )
    (net (code "235") (name "unconnected-(CMP49-OUT_13-PadP$14)") (class "Default")
      (node (ref "CMP49") (pin "P$14") (pinfunction "OUT_13_P$14") (pintype "output"))
    )
    (net (code "236") (name "unconnected-(CMP49-OUT_14-PadP$15)") (class "Default")
      (node (ref "CMP49") (pin "P$15") (pinfunction "OUT_14_P$15") (pintype "output"))
    )
    (net (code "237") (name "unconnected-(CMP49-OUT_15-PadP$16)") (class "Default")
      (node (ref "CMP49") (pin "P$16") (pinfunction "OUT_15_P$16") (pintype "output"))
    )
    (net (code "238") (name "unconnected-(CMP59-PadN0)") (class "Default")
      (node (ref "CMP59") (pin "N0") (pinfunction "N0_N0") (pintype "output"))
    )
    (net (code "239") (name "unconnected-(CMP59-PadN1)") (class "Default")
      (node (ref "CMP59") (pin "N1") (pinfunction "N1_N1") (pintype "output"))
    )
    (net (code "240") (name "unconnected-(CMP59-PadN2)") (class "Default")
      (node (ref "CMP59") (pin "N2") (pinfunction "N2_N2") (pintype "output"))
    )
    (net (code "241") (name "unconnected-(CMP59-PadN3)") (class "Default")
      (node (ref "CMP59") (pin "N3") (pinfunction "N3_N3") (pintype "output"))
    )
    (net (code "242") (name "unconnected-(CMP59-PadN4)") (class "Default")
      (node (ref "CMP59") (pin "N4") (pinfunction "N4_N4") (pintype "output"))
    )
    (net (code "243") (name "unconnected-(CMP59-PadN5)") (class "Default")
      (node (ref "CMP59") (pin "N5") (pinfunction "N5_N5") (pintype "output"))
    )
    (net (code "244") (name "unconnected-(CMP59-PadN6)") (class "Default")
      (node (ref "CMP59") (pin "N6") (pinfunction "N6_N6") (pintype "output"))
    )
    (net (code "245") (name "unconnected-(CMP59-PadN7)") (class "Default")
      (node (ref "CMP59") (pin "N7") (pinfunction "N7_N7") (pintype "output"))
    )
    (net (code "246") (name "unconnected-(CMP59-PadN8)") (class "Default")
      (node (ref "CMP59") (pin "N8") (pinfunction "N8_N8") (pintype "output"))
    )
    (net (code "247") (name "unconnected-(CMP59-PadN9)") (class "Default")
      (node (ref "CMP59") (pin "N9") (pinfunction "N9_N9") (pintype "output"))
    )
    (net (code "248") (name "unconnected-(CMP59-PadN10)") (class "Default")
      (node (ref "CMP59") (pin "N10") (pinfunction "N10_N10") (pintype "output"))
    )
    (net (code "249") (name "unconnected-(CMP59-PadN11)") (class "Default")
      (node (ref "CMP59") (pin "N11") (pinfunction "N11_N11") (pintype "output"))
    )
    (net (code "250") (name "unconnected-(CMP59-PadN12)") (class "Default")
      (node (ref "CMP59") (pin "N12") (pinfunction "N12_N12") (pintype "output"))
    )
    (net (code "251") (name "unconnected-(CMP59-PadN13)") (class "Default")
      (node (ref "CMP59") (pin "N13") (pinfunction "N13_N13") (pintype "output"))
    )
    (net (code "252") (name "unconnected-(CMP59-PadN14)") (class "Default")
      (node (ref "CMP59") (pin "N14") (pinfunction "N14_N14") (pintype "output"))
    )
    (net (code "253") (name "unconnected-(CMP59-PadN15)") (class "Default")
      (node (ref "CMP59") (pin "N15") (pinfunction "N15_N15") (pintype "output"))
    )
    (net (code "254") (name "unconnected-(CMP59-PadP0)") (class "Default")
      (node (ref "CMP59") (pin "P0") (pinfunction "P0_P0") (pintype "output"))
    )
    (net (code "255") (name "unconnected-(CMP59-PadP1)") (class "Default")
      (node (ref "CMP59") (pin "P1") (pinfunction "P1_P1") (pintype "output"))
    )
    (net (code "256") (name "unconnected-(CMP59-PadP2)") (class "Default")
      (node (ref "CMP59") (pin "P2") (pinfunction "P2_P2") (pintype "output"))
    )
    (net (code "257") (name "unconnected-(CMP59-PadP3)") (class "Default")
      (node (ref "CMP59") (pin "P3") (pinfunction "P3_P3") (pintype "output"))
    )
    (net (code "258") (name "unconnected-(CMP59-PadP8)") (class "Default")
      (node (ref "CMP59") (pin "P8") (pinfunction "P8_P8") (pintype "output"))
    )
    (net (code "259") (name "unconnected-(CMP59-PadP9)") (class "Default")
      (node (ref "CMP59") (pin "P9") (pinfunction "P9_P9") (pintype "output"))
    )
    (net (code "260") (name "unconnected-(CMP59-PadP10)") (class "Default")
      (node (ref "CMP59") (pin "P10") (pinfunction "P10_P10") (pintype "output"))
    )
    (net (code "261") (name "unconnected-(CMP59-PadP11)") (class "Default")
      (node (ref "CMP59") (pin "P11") (pinfunction "P11_P11") (pintype "output"))
    )
    (net (code "262") (name "unconnected-(CMP60-PadN0)") (class "Default")
      (node (ref "CMP60") (pin "N0") (pinfunction "N0_N0") (pintype "output"))
    )
    (net (code "263") (name "unconnected-(CMP60-PadN1)") (class "Default")
      (node (ref "CMP60") (pin "N1") (pinfunction "N1_N1") (pintype "output"))
    )
    (net (code "264") (name "unconnected-(CMP60-PadN2)") (class "Default")
      (node (ref "CMP60") (pin "N2") (pinfunction "N2_N2") (pintype "output"))
    )
    (net (code "265") (name "unconnected-(CMP60-PadN3)") (class "Default")
      (node (ref "CMP60") (pin "N3") (pinfunction "N3_N3") (pintype "output"))
    )
    (net (code "266") (name "unconnected-(CMP60-PadN4)") (class "Default")
      (node (ref "CMP60") (pin "N4") (pinfunction "N4_N4") (pintype "output"))
    )
    (net (code "267") (name "unconnected-(CMP60-PadN5)") (class "Default")
      (node (ref "CMP60") (pin "N5") (pinfunction "N5_N5") (pintype "output"))
    )
    (net (code "268") (name "unconnected-(CMP60-PadN6)") (class "Default")
      (node (ref "CMP60") (pin "N6") (pinfunction "N6_N6") (pintype "output"))
    )
    (net (code "269") (name "unconnected-(CMP60-PadN7)") (class "Default")
      (node (ref "CMP60") (pin "N7") (pinfunction "N7_N7") (pintype "output"))
    )
    (net (code "270") (name "unconnected-(CMP60-PadN8)") (class "Default")
      (node (ref "CMP60") (pin "N8") (pinfunction "N8_N8") (pintype "output"))
    )
    (net (code "271") (name "unconnected-(CMP60-PadN9)") (class "Default")
      (node (ref "CMP60") (pin "N9") (pinfunction "N9_N9") (pintype "output"))
    )
    (net (code "272") (name "unconnected-(CMP60-PadN10)") (class "Default")
      (node (ref "CMP60") (pin "N10") (pinfunction "N10_N10") (pintype "output"))
    )
    (net (code "273") (name "unconnected-(CMP60-PadN11)") (class "Default")
      (node (ref "CMP60") (pin "N11") (pinfunction "N11_N11") (pintype "output"))
    )
    (net (code "274") (name "unconnected-(CMP60-PadN12)") (class "Default")
      (node (ref "CMP60") (pin "N12") (pinfunction "N12_N12") (pintype "output"))
    )
    (net (code "275") (name "unconnected-(CMP60-PadN13)") (class "Default")
      (node (ref "CMP60") (pin "N13") (pinfunction "N13_N13") (pintype "output"))
    )
    (net (code "276") (name "unconnected-(CMP60-PadN14)") (class "Default")
      (node (ref "CMP60") (pin "N14") (pinfunction "N14_N14") (pintype "output"))
    )
    (net (code "277") (name "unconnected-(CMP60-PadN15)") (class "Default")
      (node (ref "CMP60") (pin "N15") (pinfunction "N15_N15") (pintype "output"))
    )
    (net (code "278") (name "unconnected-(CMP60-PadP2)") (class "Default")
      (node (ref "CMP60") (pin "P2") (pinfunction "P2_P2") (pintype "output"))
    )
    (net (code "279") (name "unconnected-(CMP60-PadP4)") (class "Default")
      (node (ref "CMP60") (pin "P4") (pinfunction "P4_P4") (pintype "output"))
    )
    (net (code "280") (name "unconnected-(CMP60-PadP5)") (class "Default")
      (node (ref "CMP60") (pin "P5") (pinfunction "P5_P5") (pintype "output"))
    )
    (net (code "281") (name "unconnected-(CMP60-PadP10)") (class "Default")
      (node (ref "CMP60") (pin "P10") (pinfunction "P10_P10") (pintype "output"))
    )
    (net (code "282") (name "unconnected-(CMP60-PadP12)") (class "Default")
      (node (ref "CMP60") (pin "P12") (pinfunction "P12_P12") (pintype "output"))
    )
    (net (code "283") (name "unconnected-(CMP60-PadP13)") (class "Default")
      (node (ref "CMP60") (pin "P13") (pinfunction "P13_P13") (pintype "output"))
    )
    (net (code "284") (name "unconnected-(CMP62-N-PadOUT_M)") (class "Default")
      (node (ref "CMP62") (pin "OUT_M") (pinfunction "N_OUT_M") (pintype "output"))
    )
    (net (code "285") (name "unconnected-(CMP67-PadN0)") (class "Default")
      (node (ref "CMP67") (pin "N0") (pinfunction "N0_N0") (pintype "output"))
    )
    (net (code "286") (name "unconnected-(CMP67-PadN1)") (class "Default")
      (node (ref "CMP67") (pin "N1") (pinfunction "N1_N1") (pintype "output"))
    )
    (net (code "287") (name "unconnected-(CMP67-PadN2)") (class "Default")
      (node (ref "CMP67") (pin "N2") (pinfunction "N2_N2") (pintype "output"))
    )
    (net (code "288") (name "unconnected-(CMP67-PadP0)") (class "Default")
      (node (ref "CMP67") (pin "P0") (pinfunction "P0_P0") (pintype "output"))
    )
    (net (code "289") (name "unconnected-(CMP67-PadP1)") (class "Default")
      (node (ref "CMP67") (pin "P1") (pinfunction "P1_P1") (pintype "output"))
    )
    (net (code "290") (name "unconnected-(CMP69-N-PadOUT_M)") (class "Default")
      (node (ref "CMP69") (pin "OUT_M") (pinfunction "N_OUT_M") (pintype "output"))
    )
    (net (code "291") (name "unconnected-(CMP72-N-PadOUT_M)") (class "Default")
      (node (ref "CMP72") (pin "OUT_M") (pinfunction "N_OUT_M") (pintype "output"))
    )
    (net (code "292") (name "unconnected-(CMP74-N-PadOUT_M)") (class "Default")
      (node (ref "CMP74") (pin "OUT_M") (pinfunction "N_OUT_M") (pintype "output"))
    )
    (net (code "293") (name "unconnected-(CMP76-N-PadOUT_M)") (class "Default")
      (node (ref "CMP76") (pin "OUT_M") (pinfunction "N_OUT_M") (pintype "output"))
    )
    (net (code "294") (name "unconnected-(CMP77-N-PadOUT_M)") (class "Default")
      (node (ref "CMP77") (pin "OUT_M") (pinfunction "N_OUT_M") (pintype "output"))
    )
    (net (code "295") (name "unconnected-(CMP82-PadE)") (class "Default")
      (node (ref "CMP82") (pin "E") (pinfunction "E_E") (pintype "input"))
    )
    (net (code "296") (name "unconnected-(CMP82-PadN1)") (class "Default")
      (node (ref "CMP82") (pin "N1") (pinfunction "N1_N1") (pintype "output"))
    )
    (net (code "297") (name "unconnected-(CMP82-PadN3)") (class "Default")
      (node (ref "CMP82") (pin "N3") (pinfunction "N3_N3") (pintype "output"))
    )
    (net (code "298") (name "unconnected-(CMP94-PadN0)") (class "Default")
      (node (ref "CMP94") (pin "N0") (pinfunction "N0_N0") (pintype "output"))
    )
    (net (code "299") (name "unconnected-(CMP94-PadN1)") (class "Default")
      (node (ref "CMP94") (pin "N1") (pinfunction "N1_N1") (pintype "output"))
    )
    (net (code "300") (name "unconnected-(CMP94-PadN2)") (class "Default")
      (node (ref "CMP94") (pin "N2") (pinfunction "N2_N2") (pintype "output"))
    )
    (net (code "301") (name "unconnected-(CMP94-PadN3)") (class "Default")
      (node (ref "CMP94") (pin "N3") (pinfunction "N3_N3") (pintype "output"))
    )
    (net (code "302") (name "unconnected-(CMP94-PadP1)") (class "Default")
      (node (ref "CMP94") (pin "P1") (pinfunction "P1_P1") (pintype "output"))
    )
    (net (code "303") (name "unconnected-(CMP94-PadP3)") (class "Default")
      (node (ref "CMP94") (pin "P3") (pinfunction "P3_P3") (pintype "output"))
    )
  )
)
